# LionIRVT-ADC.net
KiCad netlist of a schematic drawn in Altium Designer
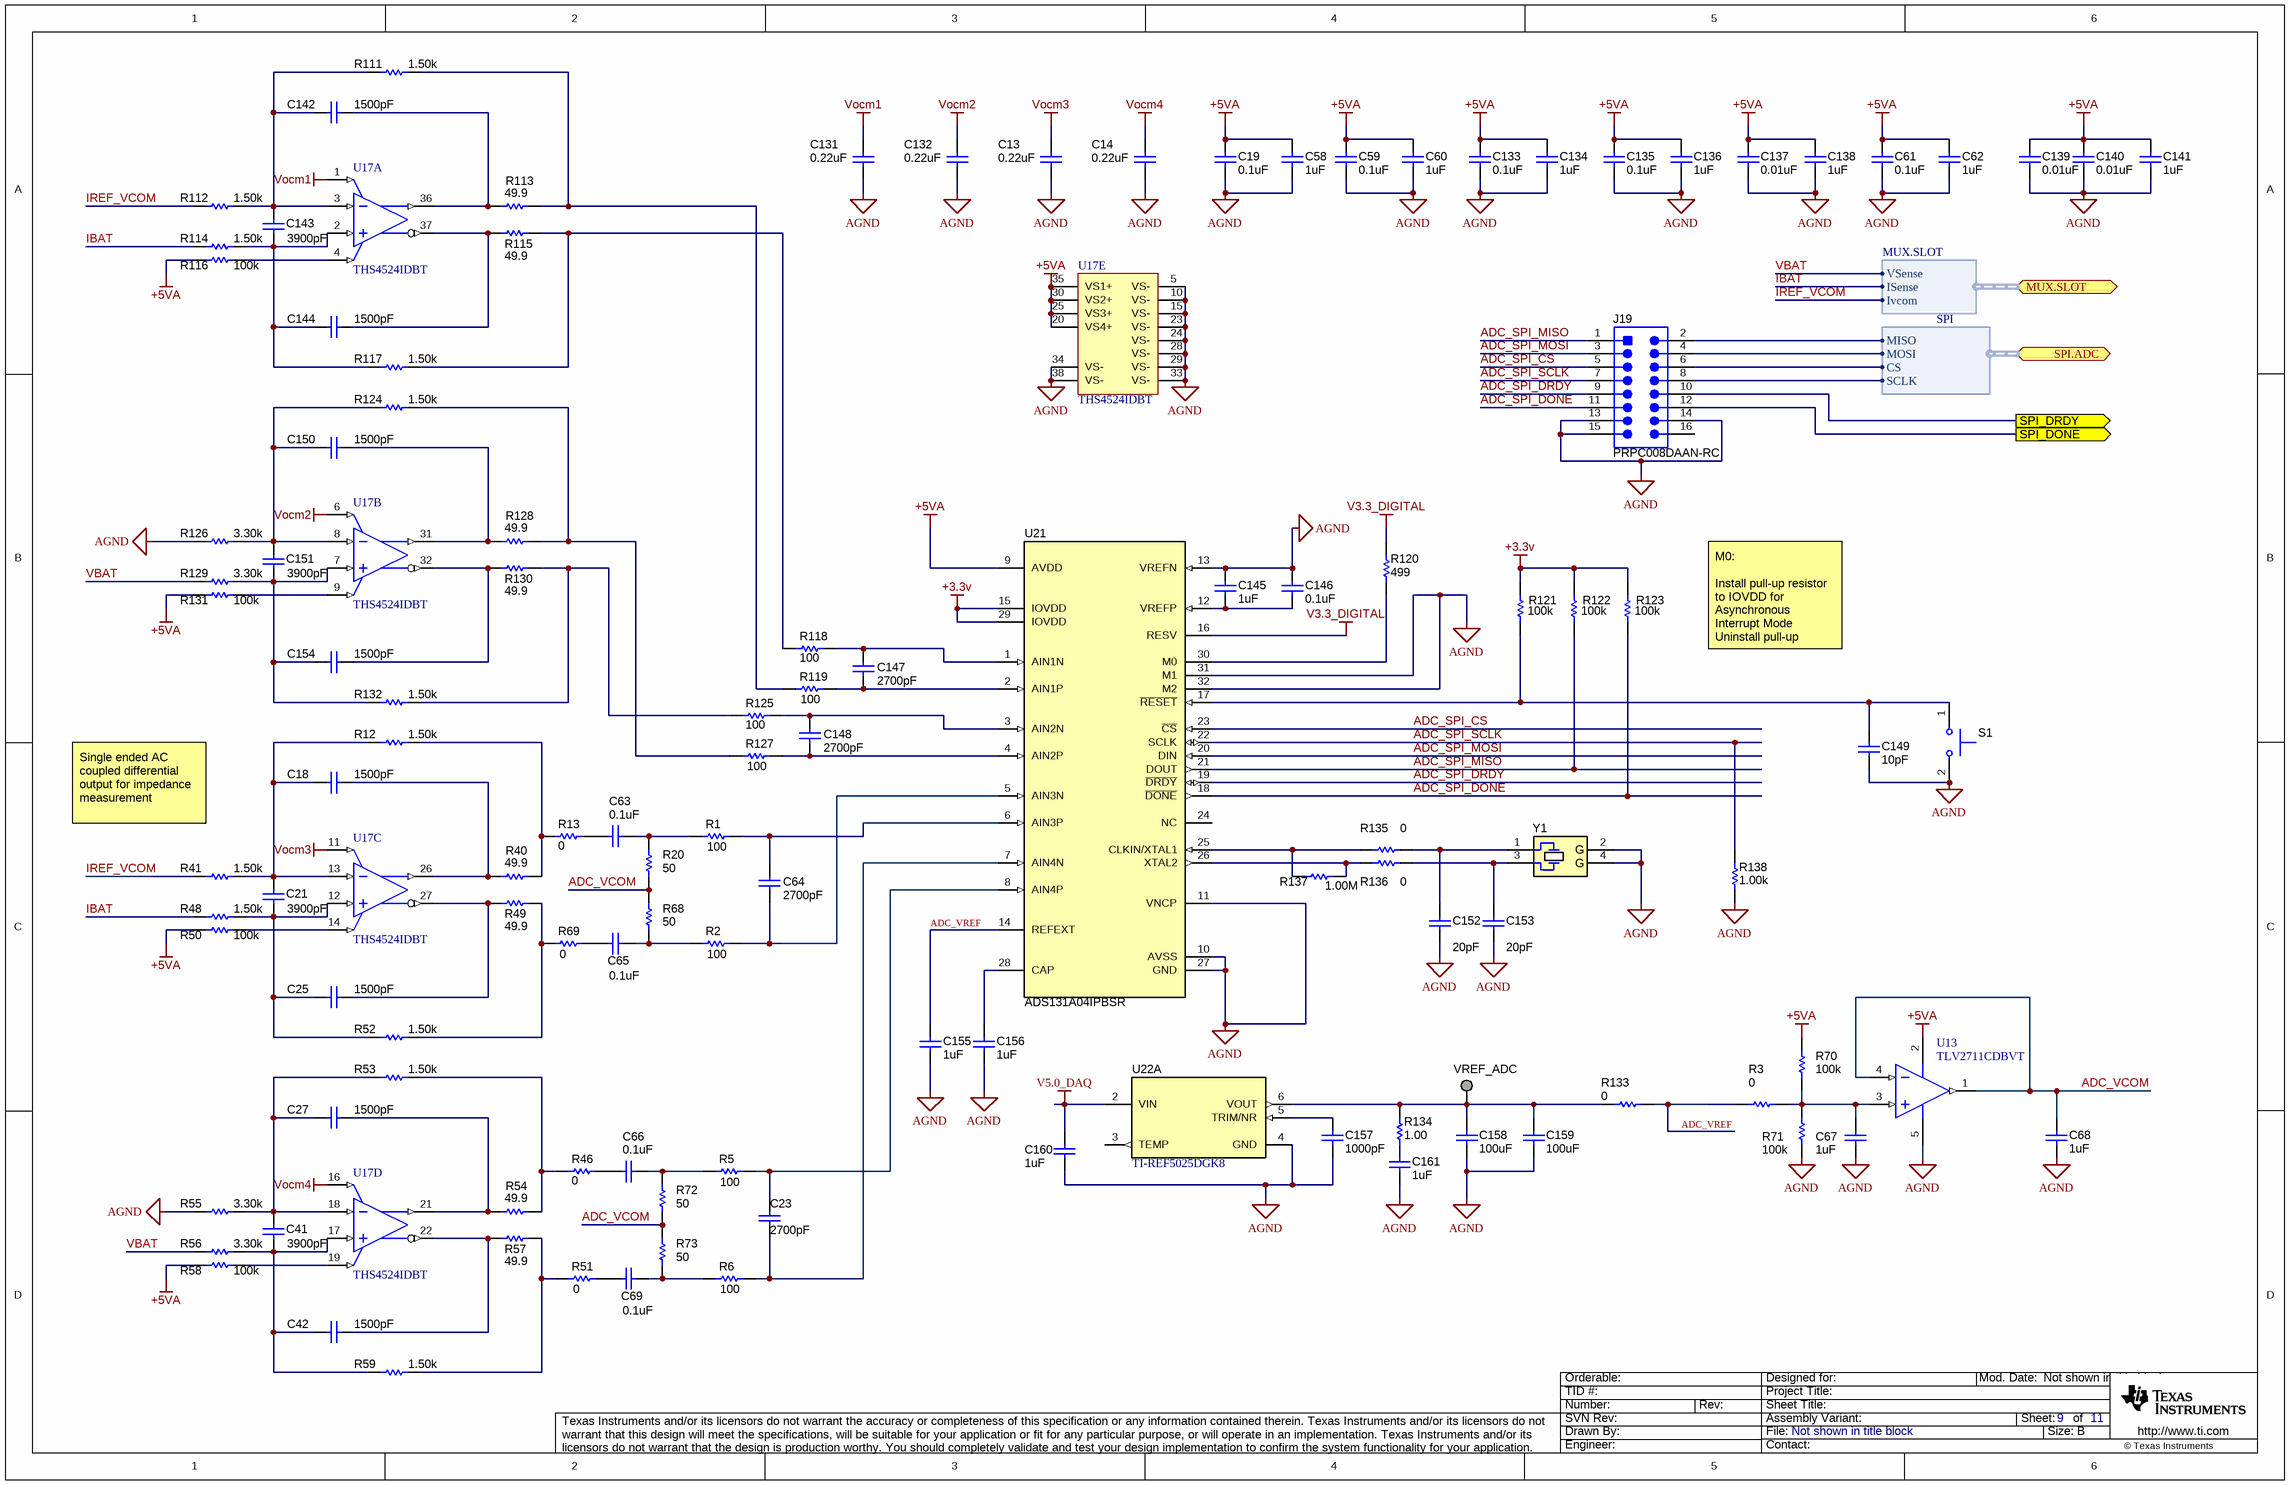
[diagram p0: LionIRVT-ADC.SchDoc]

(export (version "E")
  (design (tool "Eeschema 10.0.6"))
  (components
    (comp (ref "C13")
      (value "Capacitor")
      (footprint "0603C")
      (description "CAP, CERM, 0.22 uF, 16 V, +/- 10%, X7R, 0603")
      (fields
        (field (name "PARTNUMBER") "C0603C224K4RACTU")
        (field (name "VALUEDISPLAYED") "0.22uF")
        (field (name "MANUFACTURER") "Kemet")
        (field (name "PUBLISHER") "Texas Instruments")
      )
      (libsource (lib "SV601272A") (part "CMP-0006903-4"))
    )
    (comp (ref "C14")
      (value "Capacitor")
      (footprint "0603C")
      (description "CAP, CERM, 0.22 uF, 16 V, +/- 10%, X7R, 0603")
      (fields
        (field (name "PARTNUMBER") "C0603C224K4RACTU")
        (field (name "VALUEDISPLAYED") "0.22uF")
        (field (name "MANUFACTURER") "Kemet")
        (field (name "PUBLISHER") "Texas Instruments")
      )
      (libsource (lib "SV601272A") (part "CMP-0006903-4"))
    )
    (comp (ref "C18")
      (value "Capacitor")
      (footprint "0603C")
      (description "CAP, CERM, 1500 pF, 100 V, +/- 5%, X7R, 0603")
      (fields
        (field (name "PARTNUMBER") "06031C152JAT2A")
        (field (name "VALUEDISPLAYED") "1500pF")
        (field (name "MANUFACTURER") "AVX")
        (field (name "PUBLISHER") "Texas Instruments")
      )
      (libsource (lib "SV601272A") (part "Capacitor"))
    )
    (comp (ref "C19")
      (value "Capacitor")
      (footprint "0603C")
      (description "CAP, CERM, 0.1 uF, 25 V, +/- 5%, X7R, 0603")
      (fields
        (field (name "PARTNUMBER") "06033C104JAT2A")
        (field (name "VALUEDISPLAYED") "0.1uF")
        (field (name "MANUFACTURER") "AVX")
        (field (name "PUBLISHER") "Texas Instruments")
      )
      (libsource (lib "SV601272A") (part "CMP-0006752-5"))
    )
    (comp (ref "C21")
      (value "GRM188R72A392KA01D")
      (footprint "0603C")
      (description "CAP, CERM, 3900 pF, 100 V, +/- 10%, X7R, 0603")
      (fields
        (field (name "MANUFACTURER") "MuRata")
        (field (name "VALUEDISPLAYED") "3900pF")
        (field (name "PUBLISHER") "Texas Instruments")
      )
      (libsource (lib "SV601272A") (part "CMP-0007481-5"))
    )
    (comp (ref "C23")
      (value "Capacitor")
      (footprint "0603C")
      (description "CAP, CERM, 2700 pF, 50 V, +/- 5%, C0G/NP0, 0603")
      (fields
        (field (name "PARTNUMBER") "GRM1885C1H272JA01D")
        (field (name "VALUEDISPLAYED") "2700pF")
        (field (name "MANUFACTURER") "MuRata")
        (field (name "PUBLISHER") "Texas Instruments")
      )
      (libsource (lib "SV601272A") (part "Capacitor"))
    )
    (comp (ref "C25")
      (value "Capacitor")
      (footprint "0603C")
      (description "CAP, CERM, 1500 pF, 100 V, +/- 5%, X7R, 0603")
      (fields
        (field (name "PARTNUMBER") "06031C152JAT2A")
        (field (name "VALUEDISPLAYED") "1500pF")
        (field (name "MANUFACTURER") "AVX")
        (field (name "PUBLISHER") "Texas Instruments")
      )
      (libsource (lib "SV601272A") (part "Capacitor"))
    )
    (comp (ref "C27")
      (value "Capacitor")
      (footprint "0603C")
      (description "CAP, CERM, 1500 pF, 100 V, +/- 5%, X7R, 0603")
      (fields
        (field (name "PARTNUMBER") "06031C152JAT2A")
        (field (name "VALUEDISPLAYED") "1500pF")
        (field (name "MANUFACTURER") "AVX")
        (field (name "PUBLISHER") "Texas Instruments")
      )
      (libsource (lib "SV601272A") (part "Capacitor"))
    )
    (comp (ref "C41")
      (value "GRM188R72A392KA01D")
      (footprint "0603C")
      (description "CAP, CERM, 3900 pF, 100 V, +/- 10%, X7R, 0603")
      (fields
        (field (name "MANUFACTURER") "MuRata")
        (field (name "VALUEDISPLAYED") "3900pF")
        (field (name "PUBLISHER") "Texas Instruments")
      )
      (libsource (lib "SV601272A") (part "CMP-0007481-5"))
    )
    (comp (ref "C42")
      (value "Capacitor")
      (footprint "0603C")
      (description "CAP, CERM, 1500 pF, 100 V, +/- 5%, X7R, 0603")
      (fields
        (field (name "PARTNUMBER") "06031C152JAT2A")
        (field (name "VALUEDISPLAYED") "1500pF")
        (field (name "MANUFACTURER") "AVX")
        (field (name "PUBLISHER") "Texas Instruments")
      )
      (libsource (lib "SV601272A") (part "Capacitor"))
    )
    (comp (ref "C58")
      (value "Capacitor")
      (footprint "0603C")
      (description "CAP, CERM, 1 uF, 25 V, +/- 10%, X7R, 0603")
      (fields
        (field (name "PARTNUMBER") "GRM188R71E105KA12D")
        (field (name "VALUEDISPLAYED") "1uF")
        (field (name "MANUFACTURER") "MuRata")
        (field (name "PUBLISHER") "Texas Instruments")
      )
      (libsource (lib "SV601272A") (part "CMP-0007405-4"))
    )
    (comp (ref "C59")
      (value "Capacitor")
      (footprint "0603C")
      (description "CAP, CERM, 0.1 uF, 25 V, +/- 5%, X7R, 0603")
      (fields
        (field (name "PARTNUMBER") "06033C104JAT2A")
        (field (name "VALUEDISPLAYED") "0.1uF")
        (field (name "MANUFACTURER") "AVX")
        (field (name "PUBLISHER") "Texas Instruments")
      )
      (libsource (lib "SV601272A") (part "CMP-0006752-5"))
    )
    (comp (ref "C60")
      (value "Capacitor")
      (footprint "0603C")
      (description "CAP, CERM, 1 uF, 25 V, +/- 10%, X7R, 0603")
      (fields
        (field (name "PARTNUMBER") "GRM188R71E105KA12D")
        (field (name "VALUEDISPLAYED") "1uF")
        (field (name "MANUFACTURER") "MuRata")
        (field (name "PUBLISHER") "Texas Instruments")
      )
      (libsource (lib "SV601272A") (part "CMP-0007405-4"))
    )
    (comp (ref "C61")
      (value "Capacitor")
      (footprint "0603C")
      (description "CAP, CERM, 0.1 uF, 25 V, +/- 5%, X7R, 0603")
      (fields
        (field (name "PARTNUMBER") "06033C104JAT2A")
        (field (name "VALUEDISPLAYED") "0.1uF")
        (field (name "MANUFACTURER") "AVX")
        (field (name "PUBLISHER") "Texas Instruments")
      )
      (libsource (lib "SV601272A") (part "CMP-0006752-5"))
    )
    (comp (ref "C62")
      (value "Capacitor")
      (footprint "0603C")
      (description "CAP, CERM, 1 uF, 25 V, +/- 10%, X7R, 0603")
      (fields
        (field (name "PARTNUMBER") "GRM188R71E105KA12D")
        (field (name "VALUEDISPLAYED") "1uF")
        (field (name "MANUFACTURER") "MuRata")
        (field (name "PUBLISHER") "Texas Instruments")
      )
      (libsource (lib "SV601272A") (part "CMP-0007405-4"))
    )
    (comp (ref "C63")
      (value "Capacitor")
      (footprint "0603C")
      (description "CAP, CERM, 2700 pF, 50 V, +/- 5%, C0G/NP0, 0603")
      (fields
        (field (name "PARTNUMBER") "GRM1885C1H272JA01D")
        (field (name "VALUEDISPLAYED") "0.1uF")
        (field (name "MANUFACTURER") "MuRata")
        (field (name "PUBLISHER") "Texas Instruments")
      )
      (libsource (lib "SV601272A") (part "Capacitor"))
    )
    (comp (ref "C64")
      (value "Capacitor")
      (footprint "0603C")
      (description "CAP, CERM, 2700 pF, 50 V, +/- 5%, C0G/NP0, 0603")
      (fields
        (field (name "PARTNUMBER") "GRM1885C1H272JA01D")
        (field (name "VALUEDISPLAYED") "2700pF")
        (field (name "MANUFACTURER") "MuRata")
        (field (name "PUBLISHER") "Texas Instruments")
      )
      (libsource (lib "SV601272A") (part "Capacitor"))
    )
    (comp (ref "C65")
      (value "Capacitor")
      (footprint "0603C")
      (description "CAP, CERM, 2700 pF, 50 V, +/- 5%, C0G/NP0, 0603")
      (fields
        (field (name "PARTNUMBER") "GRM1885C1H272JA01D")
        (field (name "VALUEDISPLAYED") "0.1uF")
        (field (name "MANUFACTURER") "MuRata")
        (field (name "PUBLISHER") "Texas Instruments")
      )
      (libsource (lib "SV601272A") (part "Capacitor"))
    )
    (comp (ref "C66")
      (value "Capacitor")
      (footprint "0603C")
      (description "CAP, CERM, 2700 pF, 50 V, +/- 5%, C0G/NP0, 0603")
      (fields
        (field (name "PARTNUMBER") "GRM1885C1H272JA01D")
        (field (name "VALUEDISPLAYED") "0.1uF")
        (field (name "MANUFACTURER") "MuRata")
        (field (name "PUBLISHER") "Texas Instruments")
      )
      (libsource (lib "SV601272A") (part "Capacitor"))
    )
    (comp (ref "C67")
      (value "Capacitor")
      (footprint "0603C")
      (description "CAP, CERM, 1 uF, 25 V, +/- 10%, X7R, 0603")
      (fields
        (field (name "PARTNUMBER") "GRM188R71E105KA12D")
        (field (name "VALUEDISPLAYED") "1uF")
        (field (name "MANUFACTURER") "MuRata")
        (field (name "PUBLISHER") "Texas Instruments")
      )
      (libsource (lib "SV601272A") (part "Capacitor"))
    )
    (comp (ref "C68")
      (value "Capacitor")
      (footprint "0603C")
      (description "CAP, CERM, 1 uF, 25 V, +/- 10%, X7R, 0603")
      (fields
        (field (name "PARTNUMBER") "GRM188R71E105KA12D")
        (field (name "VALUEDISPLAYED") "1uF")
        (field (name "MANUFACTURER") "MuRata")
        (field (name "PUBLISHER") "Texas Instruments")
      )
      (libsource (lib "PMP40182") (part "Capacitor"))
    )
    (comp (ref "C69")
      (value "Capacitor")
      (footprint "0603C")
      (description "CAP, CERM, 2700 pF, 50 V, +/- 5%, C0G/NP0, 0603")
      (fields
        (field (name "PARTNUMBER") "GRM1885C1H272JA01D")
        (field (name "VALUEDISPLAYED") "0.1uF")
        (field (name "MANUFACTURER") "MuRata")
        (field (name "PUBLISHER") "Texas Instruments")
      )
      (libsource (lib "SV601272A") (part "Capacitor"))
    )
    (comp (ref "C131")
      (value "Capacitor")
      (footprint "0603C")
      (description "CAP, CERM, 0.22 uF, 16 V, +/- 10%, X7R, 0603")
      (fields
        (field (name "PARTNUMBER") "C0603C224K4RACTU")
        (field (name "VALUEDISPLAYED") "0.22uF")
        (field (name "MANUFACTURER") "Kemet")
        (field (name "PUBLISHER") "Texas Instruments")
      )
      (libsource (lib "SV601272A") (part "CMP-0006903-4"))
    )
    (comp (ref "C132")
      (value "Capacitor")
      (footprint "0603C")
      (description "CAP, CERM, 0.22 uF, 16 V, +/- 10%, X7R, 0603")
      (fields
        (field (name "PARTNUMBER") "C0603C224K4RACTU")
        (field (name "VALUEDISPLAYED") "0.22uF")
        (field (name "MANUFACTURER") "Kemet")
        (field (name "PUBLISHER") "Texas Instruments")
      )
      (libsource (lib "SV601272A") (part "CMP-0006903-4"))
    )
    (comp (ref "C133")
      (value "Capacitor")
      (footprint "0603C")
      (description "CAP, CERM, 0.1 uF, 25 V, +/- 5%, X7R, 0603")
      (fields
        (field (name "PARTNUMBER") "06033C104JAT2A")
        (field (name "VALUEDISPLAYED") "0.1uF")
        (field (name "MANUFACTURER") "AVX")
        (field (name "PUBLISHER") "Texas Instruments")
      )
      (libsource (lib "SV601272A") (part "CMP-0006752-5"))
    )
    (comp (ref "C134")
      (value "Capacitor")
      (footprint "0603C")
      (description "CAP, CERM, 1 uF, 25 V, +/- 10%, X7R, 0603")
      (fields
        (field (name "PARTNUMBER") "GRM188R71E105KA12D")
        (field (name "VALUEDISPLAYED") "1uF")
        (field (name "MANUFACTURER") "MuRata")
        (field (name "PUBLISHER") "Texas Instruments")
      )
      (libsource (lib "SV601272A") (part "CMP-0007405-4"))
    )
    (comp (ref "C135")
      (value "Capacitor")
      (footprint "0603C")
      (description "CAP, CERM, 0.1 uF, 25 V, +/- 5%, X7R, 0603")
      (fields
        (field (name "PARTNUMBER") "06033C104JAT2A")
        (field (name "VALUEDISPLAYED") "0.1uF")
        (field (name "MANUFACTURER") "AVX")
        (field (name "PUBLISHER") "Texas Instruments")
      )
      (libsource (lib "SV601272A") (part "CMP-0006752-5"))
    )
    (comp (ref "C136")
      (value "Capacitor")
      (footprint "0603C")
      (description "CAP, CERM, 1 uF, 25 V, +/- 10%, X7R, 0603")
      (fields
        (field (name "PARTNUMBER") "GRM188R71E105KA12D")
        (field (name "VALUEDISPLAYED") "1uF")
        (field (name "MANUFACTURER") "MuRata")
        (field (name "PUBLISHER") "Texas Instruments")
      )
      (libsource (lib "SV601272A") (part "CMP-0007405-4"))
    )
    (comp (ref "C137")
      (value "Capacitor")
      (footprint "0603C")
      (description "CAP, CERM, 0.01 uF, 100 V, +/- 10%, X7R, 0603")
      (fields
        (field (name "PARTNUMBER") "06031C103KAT2A")
        (field (name "VALUEDISPLAYED") "0.01uF")
        (field (name "MANUFACTURER") "AVX")
        (field (name "PUBLISHER") "Texas Instruments")
      )
      (libsource (lib "SV601272A") (part "CMP-0006727-4"))
    )
    (comp (ref "C138")
      (value "Capacitor")
      (footprint "0603C")
      (description "CAP, CERM, 1 uF, 25 V, +/- 10%, X7R, 0603")
      (fields
        (field (name "PARTNUMBER") "GRM188R71E105KA12D")
        (field (name "VALUEDISPLAYED") "1uF")
        (field (name "MANUFACTURER") "MuRata")
        (field (name "PUBLISHER") "Texas Instruments")
      )
      (libsource (lib "SV601272A") (part "CMP-0007405-4"))
    )
    (comp (ref "C139")
      (value "Capacitor")
      (footprint "0603C")
      (description "CAP, CERM, 0.01 uF, 100 V, +/- 10%, X7R, 0603")
      (fields
        (field (name "PARTNUMBER") "06031C103KAT2A")
        (field (name "VALUEDISPLAYED") "0.01uF")
        (field (name "MANUFACTURER") "AVX")
        (field (name "PUBLISHER") "Texas Instruments")
      )
      (libsource (lib "SV601272A") (part "CMP-0006727-4"))
    )
    (comp (ref "C140")
      (value "Capacitor")
      (footprint "0603C")
      (description "CAP, CERM, 0.01 uF, 100 V, +/- 10%, X7R, 0603")
      (fields
        (field (name "PARTNUMBER") "06031C103KAT2A")
        (field (name "VALUEDISPLAYED") "0.01uF")
        (field (name "MANUFACTURER") "AVX")
        (field (name "PUBLISHER") "Texas Instruments")
      )
      (libsource (lib "SV601272A") (part "CMP-0006727-4"))
    )
    (comp (ref "C141")
      (value "Capacitor")
      (footprint "0603C")
      (description "CAP, CERM, 1 uF, 25 V, +/- 10%, X7R, 0603")
      (fields
        (field (name "PARTNUMBER") "GRM188R71E105KA12D")
        (field (name "VALUEDISPLAYED") "1uF")
        (field (name "MANUFACTURER") "MuRata")
        (field (name "PUBLISHER") "Texas Instruments")
      )
      (libsource (lib "SV601272A") (part "CMP-0007405-4"))
    )
    (comp (ref "C142")
      (value "Capacitor")
      (footprint "0603C")
      (description "CAP, CERM, 1500 pF, 100 V, +/- 5%, X7R, 0603")
      (fields
        (field (name "PARTNUMBER") "06031C152JAT2A")
        (field (name "VALUEDISPLAYED") "1500pF")
        (field (name "MANUFACTURER") "AVX")
        (field (name "PUBLISHER") "Texas Instruments")
      )
      (libsource (lib "SV601272A") (part "Capacitor"))
    )
    (comp (ref "C143")
      (value "GRM188R72A392KA01D")
      (footprint "0603C")
      (description "CAP, CERM, 3900 pF, 100 V, +/- 10%, X7R, 0603")
      (fields
        (field (name "MANUFACTURER") "MuRata")
        (field (name "VALUEDISPLAYED") "3900pF")
        (field (name "PUBLISHER") "Texas Instruments")
      )
      (libsource (lib "SV601272A") (part "CMP-0007481-5"))
    )
    (comp (ref "C144")
      (value "Capacitor")
      (footprint "0603C")
      (description "CAP, CERM, 1500 pF, 100 V, +/- 5%, X7R, 0603")
      (fields
        (field (name "PARTNUMBER") "06031C152JAT2A")
        (field (name "VALUEDISPLAYED") "1500pF")
        (field (name "MANUFACTURER") "AVX")
        (field (name "PUBLISHER") "Texas Instruments")
      )
      (libsource (lib "SV601272A") (part "Capacitor"))
    )
    (comp (ref "C145")
      (value "Capacitor")
      (footprint "0603C")
      (description "CAP, CERM, 1 uF, 25 V, +/- 10%, X7R, 0603")
      (fields
        (field (name "PARTNUMBER") "GRM188R71E105KA12D")
        (field (name "VALUEDISPLAYED") "1uF")
        (field (name "MANUFACTURER") "MuRata")
        (field (name "PUBLISHER") "Texas Instruments")
      )
      (libsource (lib "SV601272A") (part "Capacitor"))
    )
    (comp (ref "C146")
      (value "Capacitor")
      (footprint "0603C")
      (description "CAP, CERM, 0.1 uF, 25 V, +/- 5%, X7R, 0603")
      (fields
        (field (name "PARTNUMBER") "06033C104JAT2A")
        (field (name "VALUEDISPLAYED") "0.1uF")
        (field (name "MANUFACTURER") "AVX")
        (field (name "PUBLISHER") "Texas Instruments")
      )
      (libsource (lib "SV601272A") (part "Capacitor"))
    )
    (comp (ref "C147")
      (value "Capacitor")
      (footprint "0603C")
      (description "CAP, CERM, 2700 pF, 50 V, +/- 5%, C0G/NP0, 0603")
      (fields
        (field (name "PARTNUMBER") "GRM1885C1H272JA01D")
        (field (name "VALUEDISPLAYED") "2700pF")
        (field (name "MANUFACTURER") "MuRata")
        (field (name "PUBLISHER") "Texas Instruments")
      )
      (libsource (lib "SV601272A") (part "Capacitor"))
    )
    (comp (ref "C148")
      (value "Capacitor")
      (footprint "0603C")
      (description "CAP, CERM, 2700 pF, 50 V, +/- 5%, C0G/NP0, 0603")
      (fields
        (field (name "PARTNUMBER") "GRM1885C1H272JA01D")
        (field (name "VALUEDISPLAYED") "2700pF")
        (field (name "MANUFACTURER") "MuRata")
        (field (name "PUBLISHER") "Texas Instruments")
      )
      (libsource (lib "SV601272A") (part "Capacitor"))
    )
    (comp (ref "C149")
      (value "Capacitor")
      (footprint "0603C")
      (description "CAP, CERM, 10 pF, 50 V, +/- 5%, C0G/NP0, 0603")
      (fields
        (field (name "PARTNUMBER") "06035A100JAT2A")
        (field (name "VALUEDISPLAYED") "10pF")
        (field (name "MANUFACTURER") "AVX")
        (field (name "PUBLISHER") "Texas Instruments")
      )
      (libsource (lib "SV601272A") (part "Capacitor"))
    )
    (comp (ref "C150")
      (value "Capacitor")
      (footprint "0603C")
      (description "CAP, CERM, 1500 pF, 100 V, +/- 5%, X7R, 0603")
      (fields
        (field (name "PARTNUMBER") "06031C152JAT2A")
        (field (name "VALUEDISPLAYED") "1500pF")
        (field (name "MANUFACTURER") "AVX")
        (field (name "PUBLISHER") "Texas Instruments")
      )
      (libsource (lib "SV601272A") (part "Capacitor"))
    )
    (comp (ref "C151")
      (value "GRM188R72A392KA01D")
      (footprint "0603C")
      (description "CAP, CERM, 3900 pF, 100 V, +/- 10%, X7R, 0603")
      (fields
        (field (name "MANUFACTURER") "MuRata")
        (field (name "VALUEDISPLAYED") "3900pF")
        (field (name "PUBLISHER") "Texas Instruments")
      )
      (libsource (lib "SV601272A") (part "CMP-0007481-5"))
    )
    (comp (ref "C152")
      (value "GRM1885C1H200JA01D")
      (footprint "0603C")
      (description "CAP, CERM, 20 pF, 50 V, +/- 5%, C0G/NP0, 0603")
      (fields
        (field (name "MANUFACTURER") "MuRata")
        (field (name "VALUEDISPLAYED") "20pF")
        (field (name "PUBLISHER") "Texas Instruments")
      )
      (libsource (lib "SV601272A") (part "CMP-0007193-4"))
    )
    (comp (ref "C153")
      (value "GRM1885C1H200JA01D")
      (footprint "0603C")
      (description "CAP, CERM, 20 pF, 50 V, +/- 5%, C0G/NP0, 0603")
      (fields
        (field (name "MANUFACTURER") "MuRata")
        (field (name "VALUEDISPLAYED") "20pF")
        (field (name "PUBLISHER") "Texas Instruments")
      )
      (libsource (lib "SV601272A") (part "CMP-0007193-4"))
    )
    (comp (ref "C154")
      (value "Capacitor")
      (footprint "0603C")
      (description "CAP, CERM, 1500 pF, 100 V, +/- 5%, X7R, 0603")
      (fields
        (field (name "PARTNUMBER") "06031C152JAT2A")
        (field (name "VALUEDISPLAYED") "1500pF")
        (field (name "MANUFACTURER") "AVX")
        (field (name "PUBLISHER") "Texas Instruments")
      )
      (libsource (lib "SV601272A") (part "Capacitor"))
    )
    (comp (ref "C155")
      (value "Capacitor")
      (footprint "0603C")
      (description "CAP, CERM, 1 uF, 25 V, +/- 10%, X7R, 0603")
      (fields
        (field (name "PARTNUMBER") "GRM188R71E105KA12D")
        (field (name "VALUEDISPLAYED") "1uF")
        (field (name "MANUFACTURER") "MuRata")
        (field (name "PUBLISHER") "Texas Instruments")
      )
      (libsource (lib "SV601272A") (part "Capacitor"))
    )
    (comp (ref "C156")
      (value "Capacitor")
      (footprint "0603C")
      (description "CAP, CERM, 1 uF, 25 V, +/- 10%, X7R, 0603")
      (fields
        (field (name "PARTNUMBER") "GRM188R71E105KA12D")
        (field (name "VALUEDISPLAYED") "1uF")
        (field (name "MANUFACTURER") "MuRata")
        (field (name "PUBLISHER") "Texas Instruments")
      )
      (libsource (lib "SV601272A") (part "Capacitor"))
    )
    (comp (ref "C157")
      (value "Capacitor")
      (footprint "0603C")
      (description "CAP, CERM, 1000 pF, 100 V, +/- 5%, X7R, 0603")
      (fields
        (field (name "PARTNUMBER") "06031C102JAT2A")
        (field (name "VALUEDISPLAYED") "1000pF")
        (field (name "MANUFACTURER") "AVX")
        (field (name "PUBLISHER") "Texas Instruments")
      )
      (libsource (lib "SV601272A") (part "Capacitor"))
    )
    (comp (ref "C158")
      (value "Capacitor")
      (footprint "1206_190")
      (description "CAP, CERM, 100 uF, 10 V, +/- 20%, X5R, 1206_190")
      (fields
        (field (name "PARTNUMBER") "C3216X5R1A107M160AC")
        (field (name "VALUEDISPLAYED") "100uF")
        (field (name "MANUFACTURER") "TDK")
        (field (name "PUBLISHER") "Texas Instruments")
      )
      (libsource (lib "SV601272A") (part "Capacitor"))
    )
    (comp (ref "C159")
      (value "Capacitor")
      (footprint "1206_190")
      (description "CAP, CERM, 100 uF, 10 V, +/- 20%, X5R, 1206_190")
      (fields
        (field (name "PARTNUMBER") "C3216X5R1A107M160AC")
        (field (name "VALUEDISPLAYED") "100uF")
        (field (name "MANUFACTURER") "TDK")
        (field (name "PUBLISHER") "Texas Instruments")
      )
      (libsource (lib "SV601272A") (part "Capacitor"))
    )
    (comp (ref "C160")
      (value "Capacitor")
      (footprint "0603C")
      (description "CAP, CERM, 1 uF, 25 V, +/- 10%, X7R, 0603")
      (fields
        (field (name "PARTNUMBER") "GRM188R71E105KA12D")
        (field (name "VALUEDISPLAYED") "1uF")
        (field (name "MANUFACTURER") "MuRata")
        (field (name "PUBLISHER") "Texas Instruments")
      )
      (libsource (lib "SV601272A") (part "Capacitor"))
    )
    (comp (ref "C161")
      (value "Capacitor")
      (footprint "0603C")
      (description "CAP, CERM, 1 uF, 25 V, +/- 10%, X7R, 0603")
      (fields
        (field (name "PARTNUMBER") "GRM188R71E105KA12D")
        (field (name "VALUEDISPLAYED") "1uF")
        (field (name "MANUFACTURER") "MuRata")
        (field (name "PUBLISHER") "Texas Instruments")
      )
      (libsource (lib "SV601272A") (part "Capacitor"))
    )
    (comp (ref "J19")
      (value "PRPC008DAAN-RC")
      (footprint "Sullins_xxxC008DAAN")
      (description "Header, 2.54mm, 8x2, Gold, TH")
      (fields
        (field (name "MANUFACTURER") "Sullins Connector Solutions")
        (field (name "PUBLISHER") "Texas Instruments")
      )
      (libsource (lib "SV601272A") (part "CMP-0054590-1"))
    )
    (comp (ref "R1")
      (value "Resistor")
      (footprint "0603R")
      (description "RES, 100, 1%, 0.1 W, AEC-Q200 Grade 0, 0603")
      (fields
        (field (name "PARTNUMBER") "CRCW0603100RFKEA")
        (field (name "MANUFACTURER") "Vishay-Dale")
        (field (name "VALUEDISPLAYED") "100")
      )
      (libsource (lib "SV601272A") (part "CMP-0021991-4"))
    )
    (comp (ref "R2")
      (value "Resistor")
      (footprint "0603R")
      (description "RES, 100, 1%, 0.1 W, AEC-Q200 Grade 0, 0603")
      (fields
        (field (name "PARTNUMBER") "CRCW0603100RFKEA")
        (field (name "MANUFACTURER") "Vishay-Dale")
        (field (name "VALUEDISPLAYED") "100")
      )
      (libsource (lib "SV601272A") (part "CMP-0021991-4"))
    )
    (comp (ref "R3")
      (value "Resistor")
      (footprint "0603R")
      (description "RES, 0, 5%, 0.1 W, 0603")
      (fields
        (field (name "PARTNUMBER") "ERJ-3GEY0R00V")
        (field (name "MANUFACTURER") "Panasonic")
        (field (name "VALUEDISPLAYED") "0")
        (field (name "PUBLISHER") "Texas Instruments")
      )
      (libsource (lib "SV601272A") (part "Resistor"))
    )
    (comp (ref "R5")
      (value "Resistor")
      (footprint "0603R")
      (description "RES, 100, 1%, 0.1 W, AEC-Q200 Grade 0, 0603")
      (fields
        (field (name "PARTNUMBER") "CRCW0603100RFKEA")
        (field (name "MANUFACTURER") "Vishay-Dale")
        (field (name "VALUEDISPLAYED") "100")
      )
      (libsource (lib "SV601272A") (part "CMP-0021991-4"))
    )
    (comp (ref "R6")
      (value "Resistor")
      (footprint "0603R")
      (description "RES, 100, 1%, 0.1 W, AEC-Q200 Grade 0, 0603")
      (fields
        (field (name "PARTNUMBER") "CRCW0603100RFKEA")
        (field (name "MANUFACTURER") "Vishay-Dale")
        (field (name "VALUEDISPLAYED") "100")
      )
      (libsource (lib "SV601272A") (part "CMP-0021991-4"))
    )
    (comp (ref "R12")
      (value "RC0603FR-071K5L")
      (footprint "0603R")
      (description "RES, 1.50 k, 1%, 0.1 W, 0603")
      (fields
        (field (name "MANUFACTURER") "Yageo America")
        (field (name "VALUEDISPLAYED") "1.50k")
        (field (name "PUBLISHER") "Texas Instruments")
      )
      (libsource (lib "SV601272A") (part "CMP-0022883-3"))
    )
    (comp (ref "R13")
      (value "Resistor")
      (footprint "0603R")
      (description "RES, 100, 1%, 0.1 W, AEC-Q200 Grade 0, 0603")
      (fields
        (field (name "PARTNUMBER") "CRCW0603100RFKEA")
        (field (name "MANUFACTURER") "Vishay-Dale")
        (field (name "VALUEDISPLAYED") "0")
      )
      (libsource (lib "SV601272A") (part "CMP-0021991-4"))
    )
    (comp (ref "R20")
      (value "Resistor")
      (footprint "0603R")
      (description "RES, 100, 1%, 0.1 W, AEC-Q200 Grade 0, 0603")
      (fields
        (field (name "PARTNUMBER") "CRCW0603100RFKEA")
        (field (name "MANUFACTURER") "Vishay-Dale")
        (field (name "VALUEDISPLAYED") "50")
      )
      (libsource (lib "SV601272A") (part "CMP-0021991-4"))
    )
    (comp (ref "R40")
      (value "Resistor")
      (footprint "0603R")
      (description "RES, 49.9, 1%, 0.1 W, AEC-Q200 Grade 0, 0603")
      (fields
        (field (name "PARTNUMBER") "CRCW060349R9FKEA")
        (field (name "MANUFACTURER") "Vishay-Dale")
        (field (name "VALUEDISPLAYED") "49.9")
      )
      (libsource (lib "SV601272A") (part "CMP-0022448-4"))
    )
    (comp (ref "R41")
      (value "RC0603FR-071K5L")
      (footprint "0603R")
      (description "RES, 1.50 k, 1%, 0.1 W, 0603")
      (fields
        (field (name "MANUFACTURER") "Yageo America")
        (field (name "VALUEDISPLAYED") "1.50k")
        (field (name "PUBLISHER") "Texas Instruments")
      )
      (libsource (lib "SV601272A") (part "CMP-0022883-3"))
    )
    (comp (ref "R46")
      (value "Resistor")
      (footprint "0603R")
      (description "RES, 100, 1%, 0.1 W, AEC-Q200 Grade 0, 0603")
      (fields
        (field (name "PARTNUMBER") "CRCW0603100RFKEA")
        (field (name "MANUFACTURER") "Vishay-Dale")
        (field (name "VALUEDISPLAYED") "0")
      )
      (libsource (lib "SV601272A") (part "CMP-0021991-4"))
    )
    (comp (ref "R48")
      (value "RC0603FR-071K5L")
      (footprint "0603R")
      (description "RES, 1.50 k, 1%, 0.1 W, 0603")
      (fields
        (field (name "MANUFACTURER") "Yageo America")
        (field (name "VALUEDISPLAYED") "1.50k")
        (field (name "PUBLISHER") "Texas Instruments")
      )
      (libsource (lib "SV601272A") (part "CMP-0022883-3"))
    )
    (comp (ref "R49")
      (value "Resistor")
      (footprint "0603R")
      (description "RES, 49.9, 1%, 0.1 W, AEC-Q200 Grade 0, 0603")
      (fields
        (field (name "PARTNUMBER") "CRCW060349R9FKEA")
        (field (name "MANUFACTURER") "Vishay-Dale")
        (field (name "VALUEDISPLAYED") "49.9")
      )
      (libsource (lib "SV601272A") (part "CMP-0022448-4"))
    )
    (comp (ref "R50")
      (value "Resistor")
      (footprint "0603R")
      (description "RES, 100 k, 1%, 0.1 W, AEC-Q200 Grade 0, 0603")
      (fields
        (field (name "PARTNUMBER") "CRCW0603100KFKEA")
        (field (name "MANUFACTURER") "Vishay-Dale")
        (field (name "VALUEDISPLAYED") "100k")
      )
      (libsource (lib "SV601272A") (part "CMP-0021990-4"))
    )
    (comp (ref "R51")
      (value "Resistor")
      (footprint "0603R")
      (description "RES, 100, 1%, 0.1 W, AEC-Q200 Grade 0, 0603")
      (fields
        (field (name "PARTNUMBER") "CRCW0603100RFKEA")
        (field (name "MANUFACTURER") "Vishay-Dale")
        (field (name "VALUEDISPLAYED") "0")
      )
      (libsource (lib "SV601272A") (part "CMP-0021991-4"))
    )
    (comp (ref "R52")
      (value "RC0603FR-071K5L")
      (footprint "0603R")
      (description "RES, 1.50 k, 1%, 0.1 W, 0603")
      (fields
        (field (name "MANUFACTURER") "Yageo America")
        (field (name "VALUEDISPLAYED") "1.50k")
        (field (name "PUBLISHER") "Texas Instruments")
      )
      (libsource (lib "SV601272A") (part "CMP-0022883-3"))
    )
    (comp (ref "R53")
      (value "RC0603FR-071K5L")
      (footprint "0603R")
      (description "RES, 1.50 k, 1%, 0.1 W, 0603")
      (fields
        (field (name "MANUFACTURER") "Yageo America")
        (field (name "VALUEDISPLAYED") "1.50k")
        (field (name "PUBLISHER") "Texas Instruments")
      )
      (libsource (lib "SV601272A") (part "CMP-0022883-3"))
    )
    (comp (ref "R54")
      (value "Resistor")
      (footprint "0603R")
      (description "RES, 49.9, 1%, 0.1 W, AEC-Q200 Grade 0, 0603")
      (fields
        (field (name "PARTNUMBER") "CRCW060349R9FKEA")
        (field (name "MANUFACTURER") "Vishay-Dale")
        (field (name "VALUEDISPLAYED") "49.9")
      )
      (libsource (lib "SV601272A") (part "CMP-0022448-4"))
    )
    (comp (ref "R55")
      (value "RC0603FR-073K3L")
      (footprint "0603R")
      (description "RES, 3.30 k, 1%, 0.1 W, 0603")
      (fields
        (field (name "VALUEDISPLAYED") "3.30k")
        (field (name "MANUFACTURER") "Yageo America")
        (field (name "PUBLISHER") "Texas Instruments")
      )
      (libsource (lib "SV601272A") (part "Resistor"))
    )
    (comp (ref "R56")
      (value "RC0603FR-073K3L")
      (footprint "0603R")
      (description "RES, 3.30 k, 1%, 0.1 W, 0603")
      (fields
        (field (name "VALUEDISPLAYED") "3.30k")
        (field (name "MANUFACTURER") "Yageo America")
        (field (name "PUBLISHER") "Texas Instruments")
      )
      (libsource (lib "SV601272A") (part "Resistor"))
    )
    (comp (ref "R57")
      (value "Resistor")
      (footprint "0603R")
      (description "RES, 49.9, 1%, 0.1 W, AEC-Q200 Grade 0, 0603")
      (fields
        (field (name "PARTNUMBER") "CRCW060349R9FKEA")
        (field (name "MANUFACTURER") "Vishay-Dale")
        (field (name "VALUEDISPLAYED") "49.9")
      )
      (libsource (lib "SV601272A") (part "Resistor"))
    )
    (comp (ref "R58")
      (value "Resistor")
      (footprint "0603R")
      (description "RES, 100 k, 1%, 0.1 W, AEC-Q200 Grade 0, 0603")
      (fields
        (field (name "PARTNUMBER") "CRCW0603100KFKEA")
        (field (name "MANUFACTURER") "Vishay-Dale")
        (field (name "VALUEDISPLAYED") "100k")
      )
      (libsource (lib "SV601272A") (part "Resistor"))
    )
    (comp (ref "R59")
      (value "RC0603FR-071K5L")
      (footprint "0603R")
      (description "RES, 1.50 k, 1%, 0.1 W, 0603")
      (fields
        (field (name "MANUFACTURER") "Yageo America")
        (field (name "VALUEDISPLAYED") "1.50k")
        (field (name "PUBLISHER") "Texas Instruments")
      )
      (libsource (lib "SV601272A") (part "Resistor"))
    )
    (comp (ref "R68")
      (value "Resistor")
      (footprint "0603R")
      (description "RES, 100, 1%, 0.1 W, AEC-Q200 Grade 0, 0603")
      (fields
        (field (name "PARTNUMBER") "CRCW0603100RFKEA")
        (field (name "MANUFACTURER") "Vishay-Dale")
        (field (name "VALUEDISPLAYED") "50")
      )
      (libsource (lib "SV601272A") (part "CMP-0021991-4"))
    )
    (comp (ref "R69")
      (value "Resistor")
      (footprint "0603R")
      (description "RES, 100, 1%, 0.1 W, AEC-Q200 Grade 0, 0603")
      (fields
        (field (name "PARTNUMBER") "CRCW0603100RFKEA")
        (field (name "MANUFACTURER") "Vishay-Dale")
        (field (name "VALUEDISPLAYED") "0")
      )
      (libsource (lib "SV601272A") (part "CMP-0021991-4"))
    )
    (comp (ref "R70")
      (value "Resistor")
      (footprint "0603R")
      (description "RES, 100 k, 1%, 0.1 W, AEC-Q200 Grade 0, 0603")
      (fields
        (field (name "PARTNUMBER") "CRCW0603100KFKEA")
        (field (name "MANUFACTURER") "Vishay-Dale")
        (field (name "VALUEDISPLAYED") "100k")
      )
      (libsource (lib "SV601272A") (part "CMP-0021990-4"))
    )
    (comp (ref "R71")
      (value "Resistor")
      (footprint "0603R")
      (description "RES, 100 k, 1%, 0.1 W, AEC-Q200 Grade 0, 0603")
      (fields
        (field (name "PARTNUMBER") "CRCW0603100KFKEA")
        (field (name "MANUFACTURER") "Vishay-Dale")
        (field (name "VALUEDISPLAYED") "100k")
      )
      (libsource (lib "SV601272A") (part "CMP-0021990-4"))
    )
    (comp (ref "R72")
      (value "Resistor")
      (footprint "0603R")
      (description "RES, 100, 1%, 0.1 W, AEC-Q200 Grade 0, 0603")
      (fields
        (field (name "PARTNUMBER") "CRCW0603100RFKEA")
        (field (name "MANUFACTURER") "Vishay-Dale")
        (field (name "VALUEDISPLAYED") "50")
      )
      (libsource (lib "SV601272A") (part "CMP-0021991-4"))
    )
    (comp (ref "R73")
      (value "Resistor")
      (footprint "0603R")
      (description "RES, 100, 1%, 0.1 W, AEC-Q200 Grade 0, 0603")
      (fields
        (field (name "PARTNUMBER") "CRCW0603100RFKEA")
        (field (name "MANUFACTURER") "Vishay-Dale")
        (field (name "VALUEDISPLAYED") "50")
      )
      (libsource (lib "SV601272A") (part "CMP-0021991-4"))
    )
    (comp (ref "R111")
      (value "RC0603FR-071K5L")
      (footprint "0603R")
      (description "RES, 1.50 k, 1%, 0.1 W, 0603")
      (fields
        (field (name "MANUFACTURER") "Yageo America")
        (field (name "VALUEDISPLAYED") "1.50k")
        (field (name "PUBLISHER") "Texas Instruments")
      )
      (libsource (lib "SV601272A") (part "CMP-0022883-3"))
    )
    (comp (ref "R112")
      (value "RC0603FR-071K5L")
      (footprint "0603R")
      (description "RES, 1.50 k, 1%, 0.1 W, 0603")
      (fields
        (field (name "MANUFACTURER") "Yageo America")
        (field (name "VALUEDISPLAYED") "1.50k")
        (field (name "PUBLISHER") "Texas Instruments")
      )
      (libsource (lib "SV601272A") (part "CMP-0022883-3"))
    )
    (comp (ref "R113")
      (value "Resistor")
      (footprint "0603R")
      (description "RES, 49.9, 1%, 0.1 W, AEC-Q200 Grade 0, 0603")
      (fields
        (field (name "PARTNUMBER") "CRCW060349R9FKEA")
        (field (name "MANUFACTURER") "Vishay-Dale")
        (field (name "VALUEDISPLAYED") "49.9")
      )
      (libsource (lib "SV601272A") (part "CMP-0022448-4"))
    )
    (comp (ref "R114")
      (value "RC0603FR-071K5L")
      (footprint "0603R")
      (description "RES, 1.50 k, 1%, 0.1 W, 0603")
      (fields
        (field (name "MANUFACTURER") "Yageo America")
        (field (name "VALUEDISPLAYED") "1.50k")
        (field (name "PUBLISHER") "Texas Instruments")
      )
      (libsource (lib "SV601272A") (part "CMP-0022883-3"))
    )
    (comp (ref "R115")
      (value "Resistor")
      (footprint "0603R")
      (description "RES, 49.9, 1%, 0.1 W, AEC-Q200 Grade 0, 0603")
      (fields
        (field (name "PARTNUMBER") "CRCW060349R9FKEA")
        (field (name "MANUFACTURER") "Vishay-Dale")
        (field (name "VALUEDISPLAYED") "49.9")
      )
      (libsource (lib "SV601272A") (part "CMP-0022448-4"))
    )
    (comp (ref "R116")
      (value "Resistor")
      (footprint "0603R")
      (description "RES, 100 k, 1%, 0.1 W, AEC-Q200 Grade 0, 0603")
      (fields
        (field (name "PARTNUMBER") "CRCW0603100KFKEA")
        (field (name "MANUFACTURER") "Vishay-Dale")
        (field (name "VALUEDISPLAYED") "100k")
      )
      (libsource (lib "SV601272A") (part "CMP-0021990-4"))
    )
    (comp (ref "R117")
      (value "RC0603FR-071K5L")
      (footprint "0603R")
      (description "RES, 1.50 k, 1%, 0.1 W, 0603")
      (fields
        (field (name "MANUFACTURER") "Yageo America")
        (field (name "VALUEDISPLAYED") "1.50k")
        (field (name "PUBLISHER") "Texas Instruments")
      )
      (libsource (lib "SV601272A") (part "CMP-0022883-3"))
    )
    (comp (ref "R118")
      (value "Resistor")
      (footprint "0603R")
      (description "RES, 100, 1%, 0.1 W, AEC-Q200 Grade 0, 0603")
      (fields
        (field (name "PARTNUMBER") "CRCW0603100RFKEA")
        (field (name "MANUFACTURER") "Vishay-Dale")
        (field (name "VALUEDISPLAYED") "100")
      )
      (libsource (lib "SV601272A") (part "CMP-0021991-4"))
    )
    (comp (ref "R119")
      (value "Resistor")
      (footprint "0603R")
      (description "RES, 100, 1%, 0.1 W, AEC-Q200 Grade 0, 0603")
      (fields
        (field (name "PARTNUMBER") "CRCW0603100RFKEA")
        (field (name "MANUFACTURER") "Vishay-Dale")
        (field (name "VALUEDISPLAYED") "100")
      )
      (libsource (lib "SV601272A") (part "CMP-0021991-4"))
    )
    (comp (ref "R120")
      (value "Resistor")
      (footprint "0603R")
      (description "RES, 499, 1%, 0.1 W, AEC-Q200 Grade 0, 0603")
      (fields
        (field (name "PARTNUMBER") "CRCW0603499RFKEA")
        (field (name "MANUFACTURER") "Vishay-Dale")
        (field (name "VALUEDISPLAYED") "499")
      )
      (libsource (lib "SV601272A") (part "CMP-0022446-5"))
    )
    (comp (ref "R121")
      (value "Resistor")
      (footprint "0603R")
      (description "RES, 100 k, 1%, 0.1 W, AEC-Q200 Grade 0, 0603")
      (fields
        (field (name "PARTNUMBER") "CRCW0603100KFKEA")
        (field (name "MANUFACTURER") "Vishay-Dale")
        (field (name "VALUEDISPLAYED") "100k")
      )
      (libsource (lib "SV601272A") (part "CMP-0021990-4"))
    )
    (comp (ref "R122")
      (value "Resistor")
      (footprint "0603R")
      (description "RES, 100 k, 1%, 0.1 W, AEC-Q200 Grade 0, 0603")
      (fields
        (field (name "PARTNUMBER") "CRCW0603100KFKEA")
        (field (name "MANUFACTURER") "Vishay-Dale")
        (field (name "VALUEDISPLAYED") "100k")
      )
      (libsource (lib "SV601272A") (part "CMP-0021990-4"))
    )
    (comp (ref "R123")
      (value "Resistor")
      (footprint "0603R")
      (description "RES, 100 k, 1%, 0.1 W, AEC-Q200 Grade 0, 0603")
      (fields
        (field (name "PARTNUMBER") "CRCW0603100KFKEA")
        (field (name "MANUFACTURER") "Vishay-Dale")
        (field (name "VALUEDISPLAYED") "100k")
      )
      (libsource (lib "SV601272A") (part "CMP-0021990-4"))
    )
    (comp (ref "R124")
      (value "RC0603FR-071K5L")
      (footprint "0603R")
      (description "RES, 1.50 k, 1%, 0.1 W, 0603")
      (fields
        (field (name "MANUFACTURER") "Yageo America")
        (field (name "VALUEDISPLAYED") "1.50k")
        (field (name "PUBLISHER") "Texas Instruments")
      )
      (libsource (lib "SV601272A") (part "CMP-0022883-3"))
    )
    (comp (ref "R125")
      (value "Resistor")
      (footprint "0603R")
      (description "RES, 100, 1%, 0.1 W, AEC-Q200 Grade 0, 0603")
      (fields
        (field (name "PARTNUMBER") "CRCW0603100RFKEA")
        (field (name "MANUFACTURER") "Vishay-Dale")
        (field (name "VALUEDISPLAYED") "100")
      )
      (libsource (lib "SV601272A") (part "CMP-0021991-4"))
    )
    (comp (ref "R126")
      (value "RC0603FR-073K3L")
      (footprint "0603R")
      (description "RES, 3.30 k, 1%, 0.1 W, 0603")
      (fields
        (field (name "VALUEDISPLAYED") "3.30k")
        (field (name "MANUFACTURER") "Yageo America")
        (field (name "PUBLISHER") "Texas Instruments")
      )
      (libsource (lib "SV601272A") (part "Resistor"))
    )
    (comp (ref "R127")
      (value "Resistor")
      (footprint "0603R")
      (description "RES, 100, 1%, 0.1 W, AEC-Q200 Grade 0, 0603")
      (fields
        (field (name "PARTNUMBER") "CRCW0603100RFKEA")
        (field (name "MANUFACTURER") "Vishay-Dale")
        (field (name "VALUEDISPLAYED") "100")
      )
      (libsource (lib "SV601272A") (part "CMP-0021991-4"))
    )
    (comp (ref "R128")
      (value "Resistor")
      (footprint "0603R")
      (description "RES, 49.9, 1%, 0.1 W, AEC-Q200 Grade 0, 0603")
      (fields
        (field (name "PARTNUMBER") "CRCW060349R9FKEA")
        (field (name "MANUFACTURER") "Vishay-Dale")
        (field (name "VALUEDISPLAYED") "49.9")
      )
      (libsource (lib "SV601272A") (part "CMP-0022448-4"))
    )
    (comp (ref "R129")
      (value "RC0603FR-073K3L")
      (footprint "0603R")
      (description "RES, 3.30 k, 1%, 0.1 W, 0603")
      (fields
        (field (name "VALUEDISPLAYED") "3.30k")
        (field (name "MANUFACTURER") "Yageo America")
        (field (name "PUBLISHER") "Texas Instruments")
      )
      (libsource (lib "SV601272A") (part "Resistor"))
    )
    (comp (ref "R130")
      (value "Resistor")
      (footprint "0603R")
      (description "RES, 49.9, 1%, 0.1 W, AEC-Q200 Grade 0, 0603")
      (fields
        (field (name "PARTNUMBER") "CRCW060349R9FKEA")
        (field (name "MANUFACTURER") "Vishay-Dale")
        (field (name "VALUEDISPLAYED") "49.9")
      )
      (libsource (lib "SV601272A") (part "Resistor"))
    )
    (comp (ref "R131")
      (value "Resistor")
      (footprint "0603R")
      (description "RES, 100 k, 1%, 0.1 W, AEC-Q200 Grade 0, 0603")
      (fields
        (field (name "PARTNUMBER") "CRCW0603100KFKEA")
        (field (name "MANUFACTURER") "Vishay-Dale")
        (field (name "VALUEDISPLAYED") "100k")
      )
      (libsource (lib "SV601272A") (part "Resistor"))
    )
    (comp (ref "R132")
      (value "RC0603FR-071K5L")
      (footprint "0603R")
      (description "RES, 1.50 k, 1%, 0.1 W, 0603")
      (fields
        (field (name "MANUFACTURER") "Yageo America")
        (field (name "VALUEDISPLAYED") "1.50k")
        (field (name "PUBLISHER") "Texas Instruments")
      )
      (libsource (lib "SV601272A") (part "Resistor"))
    )
    (comp (ref "R133")
      (value "Resistor")
      (footprint "0603R")
      (description "RES, 0, 5%, 0.1 W, 0603")
      (fields
        (field (name "PARTNUMBER") "ERJ-3GEY0R00V")
        (field (name "MANUFACTURER") "Panasonic")
        (field (name "VALUEDISPLAYED") "0")
        (field (name "PUBLISHER") "Texas Instruments")
      )
      (libsource (lib "SV601272A") (part "Resistor"))
    )
    (comp (ref "R134")
      (value "Resistor")
      (footprint "0603R")
      (description "RES, 1.00, 1%, 0.1 W, AEC-Q200 Grade 0, 0603")
      (fields
        (field (name "PARTNUMBER") "CRCW06031R00FKEA")
        (field (name "VALUEDISPLAYED") "1.00")
        (field (name "MANUFACTURER") "Vishay-Dale")
      )
      (libsource (lib "SV601272A") (part "Resistor"))
    )
    (comp (ref "R135")
      (value "Resistor")
      (footprint "0603R")
      (description "RES, 0, 5%, 0.1 W, 0603")
      (fields
        (field (name "PARTNUMBER") "ERJ-3GEY0R00V")
        (field (name "MANUFACTURER") "Panasonic")
        (field (name "VALUEDISPLAYED") "0")
        (field (name "PUBLISHER") "Texas Instruments")
      )
      (libsource (lib "SV601272A") (part "CMP-0025874-3"))
    )
    (comp (ref "R136")
      (value "Resistor")
      (footprint "0603R")
      (description "RES, 0, 5%, 0.1 W, 0603")
      (fields
        (field (name "PARTNUMBER") "ERJ-3GEY0R00V")
        (field (name "MANUFACTURER") "Panasonic")
        (field (name "VALUEDISPLAYED") "0")
        (field (name "PUBLISHER") "Texas Instruments")
      )
      (libsource (lib "SV601272A") (part "CMP-0025874-3"))
    )
    (comp (ref "R137")
      (value "Resistor")
      (footprint "0603R")
      (description "RES, 1.00 M, 1%, 0.1 W, AEC-Q200 Grade 0, 0603")
      (fields
        (field (name "PARTNUMBER") "CRCW06031M00FKEA")
        (field (name "MANUFACTURER") "Vishay-Dale")
        (field (name "VALUEDISPLAYED") "1.00M")
      )
      (libsource (lib "SV601272A") (part "CMP-0022138-4"))
    )
    (comp (ref "R138")
      (value "Resistor")
      (footprint "0603R")
      (description "RES, 1.00 k, 1%, 0.1 W, AEC-Q200 Grade 0, 0603")
      (fields
        (field (name "PARTNUMBER") "CRCW06031K00FKEA")
        (field (name "MANUFACTURER") "Vishay-Dale")
        (field (name "VALUEDISPLAYED") "1.00k")
      )
      (libsource (lib "SV601272A") (part "CMP-0022109-5"))
    )
    (comp (ref "S1")
      (value "Switch_PushButton")
      (footprint "SW_TL1015AF160QG")
      (description "Switch, Tactile, SPST-NO, 0.05A, 12V, SMT")
      (fields
        (field (name "PARTNUMBER") "TL1015AF160QG")
        (field (name "MANUFACTURER") "E-Switch")
        (field (name "PUBLISHER") "Texas Instruments")
      )
      (libsource (lib "SV601272A") (part "Switch_PushButton"))
    )
    (comp (ref "U13")
      (value "TLV2711CDBVT")
      (footprint "DBV0005A_M")
      (fields (field (name "MANUFACTURER") "Texas Instruments"))
      (libsource (lib "Altium Content Vault") (part "TI-TLV27X1DBV5"))
    )
    (comp (ref "U17")
      (value "THS4524IDBT")
      (footprint "DBT0038A_M")
      (fields (field (name "MANUFACTURER") "Texas Instruments"))
      (libsource (lib "Altium Content Vault") (part "TI-THS4524-DBT38"))
    )
    (comp (ref "U21")
      (value "ADS131A04IPBSR")
      (footprint "PBS0032A_L")
      (description "24-Bit, 128kSPS, 4-Ch, Simultaneous Sampling, Delta-Sigma ADC, PBS0032A (TQFP-32)")
      (fields
        (field (name "ALTERNATE PARTNUMBER") "ADS131A04IPBS")
        (field (name "PARTNUMBER") "ADS131A04IPBSR")
        (field (name "MANUFACTURER") "Texas Instruments")
        (field (name "PUBLISHER") "Texas Instruments")
      )
      (libsource (lib "SV601272A") (part "ADS131A04"))
    )
    (comp (ref "U22")
      (value "TI-REF5025DGK8")
      (footprint "DGK0008A_N")
      (fields (field (name "PARTNUMBER") "REF5025IDGKR") (field (name "MANUFACTURER") "Texas Instruments"))
      (libsource (lib "SV601272A") (part "CMP-0032584-1"))
    )
    (comp (ref "VREF_ADC")
      (value "Pogo Pad")
      (footprint "PogoPad")
      (description "Pad for Pogo Pin Connector")
      (fields (field (name "SYMBOLCREATOR") "codlsc") (field (name "PUBLISHER") "Texas Instruments"))
      (libsource (lib "SV601272A") (part "PogoPad"))
    )
    (comp (ref "Y1")
      (value "XTAL_4P_13_G24")
      (footprint "CTS_407")
      (description "Crystal, 16.384 MHz, 20 pF, SMD")
      (fields
        (field (name "PARTNUMBER") "407F35E016M3840")
        (field (name "MANUFACTURER") "CTS Electrocomponents")
      )
      (libsource (lib "SV601272A") (part "XTAL_4P_13_G24"))
    )
  )
  (nets
    (net (code "3") (name "+3.3v") (class "Default")
      (node (ref "R121") (pin "2") (pinfunction "2_2") (pintype "passive"))
      (node (ref "R122") (pin "2") (pinfunction "2_2") (pintype "passive"))
      (node (ref "R123") (pin "2") (pinfunction "2_2") (pintype "passive"))
      (node (ref "U21") (pin "15") (pinfunction "IOVDD_15") (pintype "power_in"))
      (node (ref "U21") (pin "29") (pinfunction "IOVDD_29") (pintype "power_in"))
    )
    (net (code "4") (name "+5VA") (class "Default")
      (node (ref "C133") (pin "1") (pinfunction "1_1") (pintype "passive"))
      (node (ref "C134") (pin "1") (pinfunction "1_1") (pintype "passive"))
      (node (ref "C135") (pin "1") (pinfunction "1_1") (pintype "passive"))
      (node (ref "C136") (pin "1") (pinfunction "1_1") (pintype "passive"))
      (node (ref "C137") (pin "1") (pinfunction "1_1") (pintype "passive"))
      (node (ref "C138") (pin "1") (pinfunction "1_1") (pintype "passive"))
      (node (ref "C139") (pin "1") (pinfunction "1_1") (pintype "passive"))
      (node (ref "C140") (pin "1") (pinfunction "1_1") (pintype "passive"))
      (node (ref "C141") (pin "1") (pinfunction "1_1") (pintype "passive"))
      (node (ref "C19") (pin "1") (pinfunction "1_1") (pintype "passive"))
      (node (ref "C58") (pin "1") (pinfunction "1_1") (pintype "passive"))
      (node (ref "C59") (pin "1") (pinfunction "1_1") (pintype "passive"))
      (node (ref "C60") (pin "1") (pinfunction "1_1") (pintype "passive"))
      (node (ref "C61") (pin "1") (pinfunction "1_1") (pintype "passive"))
      (node (ref "C62") (pin "1") (pinfunction "1_1") (pintype "passive"))
      (node (ref "R116") (pin "2") (pinfunction "2_2") (pintype "passive"))
      (node (ref "R131") (pin "2") (pinfunction "2_2") (pintype "passive"))
      (node (ref "R50") (pin "2") (pinfunction "2_2") (pintype "passive"))
      (node (ref "R58") (pin "2") (pinfunction "2_2") (pintype "passive"))
      (node (ref "R70") (pin "1") (pinfunction "1_1") (pintype "passive"))
      (node (ref "U13") (pin "2") (pinfunction "VDD+_2") (pintype "power_in"))
      (node (ref "U17") (pin "20") (pinfunction "VS4+_20") (pintype "power_in"))
      (node (ref "U17") (pin "25") (pinfunction "VS3+_25") (pintype "power_in"))
      (node (ref "U17") (pin "30") (pinfunction "VS2+_30") (pintype "power_in"))
      (node (ref "U17") (pin "35") (pinfunction "VS1+_35") (pintype "power_in"))
      (node (ref "U21") (pin "9") (pinfunction "AVDD_9") (pintype "power_in"))
    )
    (net (code "5") (name "/ADC_SPI_CS") (class "Default")
      (node (ref "J19") (pin "5") (pinfunction "5_5") (pintype "passive"))
      (node (ref "U21") (pin "23") (pinfunction "CS_23") (pintype "input"))
    )
    (net (code "6") (name "/ADC_SPI_DONE") (class "Default")
      (node (ref "J19") (pin "11") (pinfunction "11_11") (pintype "passive"))
      (node (ref "R123") (pin "1") (pinfunction "1_1") (pintype "passive"))
      (node (ref "U21") (pin "18") (pinfunction "DONE_18") (pintype "output"))
    )
    (net (code "7") (name "/ADC_SPI_DRDY") (class "Default")
      (node (ref "J19") (pin "9") (pinfunction "9_9") (pintype "passive"))
      (node (ref "U21") (pin "19") (pinfunction "DRDY_19") (pintype "bidirectional"))
    )
    (net (code "8") (name "/ADC_SPI_MISO") (class "Default")
      (node (ref "J19") (pin "1") (pinfunction "1_1") (pintype "passive"))
      (node (ref "R122") (pin "1") (pinfunction "1_1") (pintype "passive"))
      (node (ref "U21") (pin "21") (pinfunction "DOUT_21") (pintype "output"))
    )
    (net (code "9") (name "/ADC_SPI_MOSI") (class "Default")
      (node (ref "J19") (pin "3") (pinfunction "3_3") (pintype "passive"))
      (node (ref "U21") (pin "20") (pinfunction "DIN_20") (pintype "input"))
    )
    (net (code "10") (name "/ADC_SPI_SCLK") (class "Default")
      (node (ref "J19") (pin "7") (pinfunction "7_7") (pintype "passive"))
      (node (ref "R138") (pin "2") (pinfunction "2_2") (pintype "passive"))
      (node (ref "U21") (pin "22") (pinfunction "SCLK_22") (pintype "bidirectional"))
    )
    (net (code "11") (name "/ADC_VCOM") (class "Default")
      (node (ref "C68") (pin "1") (pinfunction "1_1") (pintype "passive"))
      (node (ref "R20") (pin "1") (pinfunction "1_1") (pintype "passive"))
      (node (ref "R68") (pin "2") (pinfunction "2_2") (pintype "passive"))
      (node (ref "R72") (pin "1") (pinfunction "1_1") (pintype "passive"))
      (node (ref "R73") (pin "2") (pinfunction "2_2") (pintype "passive"))
      (node (ref "U13") (pin "1") (pinfunction "OUT_1") (pintype "output"))
      (node (ref "U13") (pin "4") (pinfunction "IN-_4") (pintype "input"))
    )
    (net (code "12") (name "/ADC_VREF") (class "Default")
      (node (ref "C155") (pin "1") (pinfunction "1_1") (pintype "passive"))
      (node (ref "R133") (pin "2") (pinfunction "2_2") (pintype "passive"))
      (node (ref "R3") (pin "1") (pinfunction "1_1") (pintype "passive"))
      (node (ref "U21") (pin "14") (pinfunction "REFEXT_14") (pintype "passive"))
    )
    (net (code "13") (name "/CS") (class "Default")
      (node (ref "J19") (pin "6") (pinfunction "6_6") (pintype "passive"))
    )
    (net (code "14") (name "/IBAT") (class "Default")
      (node (ref "R114") (pin "1") (pinfunction "1_1") (pintype "passive"))
      (node (ref "R48") (pin "1") (pinfunction "1_1") (pintype "passive"))
    )
    (net (code "15") (name "/IREF_VCOM") (class "Default")
      (node (ref "R112") (pin "1") (pinfunction "1_1") (pintype "passive"))
      (node (ref "R41") (pin "1") (pinfunction "1_1") (pintype "passive"))
    )
    (net (code "16") (name "/MISO") (class "Default")
      (node (ref "J19") (pin "2") (pinfunction "2_2") (pintype "passive"))
    )
    (net (code "17") (name "/MOSI") (class "Default")
      (node (ref "J19") (pin "4") (pinfunction "4_4") (pintype "passive"))
    )
    (net (code "18") (name "/SCLK") (class "Default")
      (node (ref "J19") (pin "8") (pinfunction "8_8") (pintype "passive"))
    )
    (net (code "19") (name "/SPI_DONE") (class "Default")
      (node (ref "J19") (pin "12") (pinfunction "12_12") (pintype "passive"))
    )
    (net (code "20") (name "/SPI_DRDY") (class "Default")
      (node (ref "J19") (pin "10") (pinfunction "10_10") (pintype "passive"))
    )
    (net (code "21") (name "/VBAT") (class "Default")
      (node (ref "R129") (pin "1") (pinfunction "1_1") (pintype "passive"))
      (node (ref "R56") (pin "1") (pinfunction "1_1") (pintype "passive"))
    )
    (net (code "24") (name "AGND") (class "Default")
      (node (ref "C13") (pin "2") (pinfunction "2_2") (pintype "passive"))
      (node (ref "C131") (pin "2") (pinfunction "2_2") (pintype "passive"))
      (node (ref "C132") (pin "2") (pinfunction "2_2") (pintype "passive"))
      (node (ref "C133") (pin "2") (pinfunction "2_2") (pintype "passive"))
      (node (ref "C134") (pin "2") (pinfunction "2_2") (pintype "passive"))
      (node (ref "C135") (pin "2") (pinfunction "2_2") (pintype "passive"))
      (node (ref "C136") (pin "2") (pinfunction "2_2") (pintype "passive"))
      (node (ref "C137") (pin "2") (pinfunction "2_2") (pintype "passive"))
      (node (ref "C138") (pin "2") (pinfunction "2_2") (pintype "passive"))
      (node (ref "C139") (pin "2") (pinfunction "2_2") (pintype "passive"))
      (node (ref "C14") (pin "2") (pinfunction "2_2") (pintype "passive"))
      (node (ref "C140") (pin "2") (pinfunction "2_2") (pintype "passive"))
      (node (ref "C141") (pin "2") (pinfunction "2_2") (pintype "passive"))
      (node (ref "C145") (pin "1") (pinfunction "1_1") (pintype "passive"))
      (node (ref "C146") (pin "1") (pinfunction "1_1") (pintype "passive"))
      (node (ref "C149") (pin "1") (pinfunction "1_1") (pintype "passive"))
      (node (ref "C152") (pin "2") (pinfunction "2_2") (pintype "passive"))
      (node (ref "C153") (pin "2") (pinfunction "2_2") (pintype "passive"))
      (node (ref "C155") (pin "2") (pinfunction "2_2") (pintype "passive"))
      (node (ref "C156") (pin "2") (pinfunction "2_2") (pintype "passive"))
      (node (ref "C157") (pin "2") (pinfunction "2_2") (pintype "passive"))
      (node (ref "C158") (pin "2") (pinfunction "2_2") (pintype "passive"))
      (node (ref "C159") (pin "2") (pinfunction "2_2") (pintype "passive"))
      (node (ref "C160") (pin "2") (pinfunction "2_2") (pintype "passive"))
      (node (ref "C161") (pin "2") (pinfunction "2_2") (pintype "passive"))
      (node (ref "C19") (pin "2") (pinfunction "2_2") (pintype "passive"))
      (node (ref "C58") (pin "2") (pinfunction "2_2") (pintype "passive"))
      (node (ref "C59") (pin "2") (pinfunction "2_2") (pintype "passive"))
      (node (ref "C60") (pin "2") (pinfunction "2_2") (pintype "passive"))
      (node (ref "C61") (pin "2") (pinfunction "2_2") (pintype "passive"))
      (node (ref "C62") (pin "2") (pinfunction "2_2") (pintype "passive"))
      (node (ref "C67") (pin "2") (pinfunction "2_2") (pintype "passive"))
      (node (ref "C68") (pin "2") (pinfunction "2_2") (pintype "passive"))
      (node (ref "J19") (pin "13") (pinfunction "13_13") (pintype "passive"))
      (node (ref "J19") (pin "14") (pinfunction "14_14") (pintype "passive"))
      (node (ref "J19") (pin "15") (pinfunction "15_15") (pintype "passive"))
      (node (ref "R126") (pin "1") (pinfunction "1_1") (pintype "passive"))
      (node (ref "R138") (pin "1") (pinfunction "1_1") (pintype "passive"))
      (node (ref "R55") (pin "1") (pinfunction "1_1") (pintype "passive"))
      (node (ref "R71") (pin "2") (pinfunction "2_2") (pintype "passive"))
      (node (ref "S1") (pin "2") (pinfunction "2_2") (pintype "passive"))
      (node (ref "U13") (pin "5") (pinfunction "VDD-/GND_5") (pintype "power_in"))
      (node (ref "U17") (pin "10") (pinfunction "VS-_10") (pintype "power_in"))
      (node (ref "U17") (pin "15") (pinfunction "VS-_15") (pintype "power_in"))
      (node (ref "U17") (pin "23") (pinfunction "VS-_23") (pintype "power_in"))
      (node (ref "U17") (pin "24") (pinfunction "VS-_24") (pintype "power_in"))
      (node (ref "U17") (pin "28") (pinfunction "VS-_28") (pintype "power_in"))
      (node (ref "U17") (pin "29") (pinfunction "VS-_29") (pintype "power_in"))
      (node (ref "U17") (pin "33") (pinfunction "VS-_33") (pintype "power_in"))
      (node (ref "U17") (pin "34") (pinfunction "VS-_34") (pintype "power_in"))
      (node (ref "U17") (pin "38") (pinfunction "VS-_38") (pintype "power_in"))
      (node (ref "U17") (pin "5") (pinfunction "VS-_5") (pintype "power_in"))
      (node (ref "U21") (pin "10") (pinfunction "AVSS_10") (pintype "power_in"))
      (node (ref "U21") (pin "11") (pinfunction "VNCP_11") (pintype "power_in"))
      (node (ref "U21") (pin "13") (pinfunction "VREFN_13") (pintype "input"))
      (node (ref "U21") (pin "27") (pinfunction "GND_27") (pintype "power_in"))
      (node (ref "U21") (pin "31") (pinfunction "M1_31") (pintype "passive"))
      (node (ref "U21") (pin "32") (pinfunction "M2_32") (pintype "passive"))
      (node (ref "U22") (pin "4") (pinfunction "GND_4") (pintype "power_in"))
      (node (ref "Y1") (pin "2") (pinfunction "GND_2") (pintype "power_in"))
      (node (ref "Y1") (pin "4") (pinfunction "GND_4") (pintype "power_in"))
    )
    (net (code "25") (name "Net-(C63-Pad1)") (class "Default")
      (node (ref "C63") (pin "1") (pinfunction "1_1") (pintype "passive"))
      (node (ref "R13") (pin "2") (pinfunction "2_2") (pintype "passive"))
    )
    (net (code "26") (name "Net-(C63-Pad2)") (class "Default")
      (node (ref "C63") (pin "2") (pinfunction "2_2") (pintype "passive"))
      (node (ref "R1") (pin "1") (pinfunction "1_1") (pintype "passive"))
      (node (ref "R20") (pin "2") (pinfunction "2_2") (pintype "passive"))
    )
    (net (code "27") (name "Net-(C65-Pad1)") (class "Default")
      (node (ref "C65") (pin "1") (pinfunction "1_1") (pintype "passive"))
      (node (ref "R69") (pin "2") (pinfunction "2_2") (pintype "passive"))
    )
    (net (code "28") (name "Net-(C65-Pad2)") (class "Default")
      (node (ref "C65") (pin "2") (pinfunction "2_2") (pintype "passive"))
      (node (ref "R2") (pin "1") (pinfunction "1_1") (pintype "passive"))
      (node (ref "R68") (pin "1") (pinfunction "1_1") (pintype "passive"))
    )
    (net (code "29") (name "Net-(C66-Pad1)") (class "Default")
      (node (ref "C66") (pin "1") (pinfunction "1_1") (pintype "passive"))
      (node (ref "R46") (pin "2") (pinfunction "2_2") (pintype "passive"))
    )
    (net (code "30") (name "Net-(C66-Pad2)") (class "Default")
      (node (ref "C66") (pin "2") (pinfunction "2_2") (pintype "passive"))
      (node (ref "R5") (pin "1") (pinfunction "1_1") (pintype "passive"))
      (node (ref "R72") (pin "2") (pinfunction "2_2") (pintype "passive"))
    )
    (net (code "31") (name "Net-(C69-Pad1)") (class "Default")
      (node (ref "C69") (pin "1") (pinfunction "1_1") (pintype "passive"))
      (node (ref "R51") (pin "2") (pinfunction "2_2") (pintype "passive"))
    )
    (net (code "32") (name "Net-(C69-Pad2)") (class "Default")
      (node (ref "C69") (pin "2") (pinfunction "2_2") (pintype "passive"))
      (node (ref "R6") (pin "1") (pinfunction "1_1") (pintype "passive"))
      (node (ref "R73") (pin "1") (pinfunction "1_1") (pintype "passive"))
    )
    (net (code "33") (name "Net-(C152-Pad1)") (class "Default")
      (node (ref "C152") (pin "1") (pinfunction "1_1") (pintype "passive"))
      (node (ref "R135") (pin "2") (pinfunction "2_2") (pintype "passive"))
      (node (ref "Y1") (pin "1") (pinfunction "1_1") (pintype "passive"))
    )
    (net (code "34") (name "Net-(C153-Pad1)") (class "Default")
      (node (ref "C153") (pin "1") (pinfunction "1_1") (pintype "passive"))
      (node (ref "R136") (pin "1") (pinfunction "1_1") (pintype "passive"))
      (node (ref "Y1") (pin "3") (pinfunction "3_3") (pintype "passive"))
    )
    (net (code "35") (name "Net-(C161-Pad1)") (class "Default")
      (node (ref "C161") (pin "1") (pinfunction "1_1") (pintype "passive"))
      (node (ref "R134") (pin "1") (pinfunction "1_1") (pintype "passive"))
    )
    (net (code "36") (name "Net-(R12-Pad2)") (class "Default")
      (node (ref "R12") (pin "2") (pinfunction "2_2") (pintype "passive"))
      (node (ref "R13") (pin "1") (pinfunction "1_1") (pintype "passive"))
      (node (ref "R40") (pin "2") (pinfunction "2_2") (pintype "passive"))
    )
    (net (code "37") (name "Net-(R46-Pad1)") (class "Default")
      (node (ref "R46") (pin "1") (pinfunction "1_1") (pintype "passive"))
      (node (ref "R53") (pin "2") (pinfunction "2_2") (pintype "passive"))
      (node (ref "R54") (pin "2") (pinfunction "2_2") (pintype "passive"))
    )
    (net (code "38") (name "Net-(R49-Pad2)") (class "Default")
      (node (ref "R49") (pin "2") (pinfunction "2_2") (pintype "passive"))
      (node (ref "R52") (pin "2") (pinfunction "2_2") (pintype "passive"))
      (node (ref "R69") (pin "1") (pinfunction "1_1") (pintype "passive"))
    )
    (net (code "39") (name "Net-(R51-Pad1)") (class "Default")
      (node (ref "R51") (pin "1") (pinfunction "1_1") (pintype "passive"))
      (node (ref "R57") (pin "2") (pinfunction "2_2") (pintype "passive"))
      (node (ref "R59") (pin "2") (pinfunction "2_2") (pintype "passive"))
    )
    (net (code "40") (name "Net-(R111-Pad2)") (class "Default")
      (node (ref "R111") (pin "2") (pinfunction "2_2") (pintype "passive"))
      (node (ref "R113") (pin "2") (pinfunction "2_2") (pintype "passive"))
      (node (ref "R119") (pin "1") (pinfunction "1_1") (pintype "passive"))
    )
    (net (code "41") (name "Net-(R115-Pad2)") (class "Default")
      (node (ref "R115") (pin "2") (pinfunction "2_2") (pintype "passive"))
      (node (ref "R117") (pin "2") (pinfunction "2_2") (pintype "passive"))
      (node (ref "R118") (pin "1") (pinfunction "1_1") (pintype "passive"))
    )
    (net (code "42") (name "Net-(R124-Pad2)") (class "Default")
      (node (ref "R124") (pin "2") (pinfunction "2_2") (pintype "passive"))
      (node (ref "R127") (pin "1") (pinfunction "1_1") (pintype "passive"))
      (node (ref "R128") (pin "2") (pinfunction "2_2") (pintype "passive"))
    )
    (net (code "43") (name "Net-(R125-Pad1)") (class "Default")
      (node (ref "R125") (pin "1") (pinfunction "1_1") (pintype "passive"))
      (node (ref "R130") (pin "2") (pinfunction "2_2") (pintype "passive"))
      (node (ref "R132") (pin "2") (pinfunction "2_2") (pintype "passive"))
    )
    (net (code "44") (name "Net-(U13-IN+)") (class "Default")
      (node (ref "C67") (pin "1") (pinfunction "1_1") (pintype "passive"))
      (node (ref "R3") (pin "2") (pinfunction "2_2") (pintype "passive"))
      (node (ref "R70") (pin "2") (pinfunction "2_2") (pintype "passive"))
      (node (ref "R71") (pin "1") (pinfunction "1_1") (pintype "passive"))
      (node (ref "U13") (pin "3") (pinfunction "IN+_3") (pintype "input"))
    )
    (net (code "45") (name "Net-(U17A-VIN1+)") (class "Default")
      (node (ref "C143") (pin "2") (pinfunction "2_2") (pintype "passive"))
      (node (ref "C144") (pin "1") (pinfunction "1_1") (pintype "passive"))
      (node (ref "R114") (pin "2") (pinfunction "2_2") (pintype "passive"))
      (node (ref "R117") (pin "1") (pinfunction "1_1") (pintype "passive"))
      (node (ref "U17") (pin "2") (pinfunction "VIN1+_2") (pintype "input"))
    )
    (net (code "46") (name "Net-(U17A-VIN1-)") (class "Default")
      (node (ref "C142") (pin "1") (pinfunction "1_1") (pintype "passive"))
      (node (ref "C143") (pin "1") (pinfunction "1_1") (pintype "passive"))
      (node (ref "R111") (pin "1") (pinfunction "1_1") (pintype "passive"))
      (node (ref "R112") (pin "2") (pinfunction "2_2") (pintype "passive"))
      (node (ref "U17") (pin "3") (pinfunction "VIN1-_3") (pintype "input"))
    )
    (net (code "47") (name "Net-(U17A-VOCM1)") (class "Default")
      (node (ref "R116") (pin "1") (pinfunction "1_1") (pintype "passive"))
      (node (ref "U17") (pin "4") (pinfunction "VOCM1_4") (pintype "input"))
    )
    (net (code "48") (name "Net-(U17A-VOUT1+)") (class "Default")
      (node (ref "C142") (pin "2") (pinfunction "2_2") (pintype "passive"))
      (node (ref "R113") (pin "1") (pinfunction "1_1") (pintype "passive"))
      (node (ref "U17") (pin "36") (pinfunction "VOUT1+_36") (pintype "output"))
    )
    (net (code "49") (name "Net-(U17A-VOUT1-)") (class "Default")
      (node (ref "C144") (pin "2") (pinfunction "2_2") (pintype "passive"))
      (node (ref "R115") (pin "1") (pinfunction "1_1") (pintype "passive"))
      (node (ref "U17") (pin "37") (pinfunction "VOUT1-_37") (pintype "output"))
    )
    (net (code "50") (name "Net-(U17B-VIN2+)") (class "Default")
      (node (ref "C151") (pin "2") (pinfunction "2_2") (pintype "passive"))
      (node (ref "C154") (pin "1") (pinfunction "1_1") (pintype "passive"))
      (node (ref "R129") (pin "2") (pinfunction "2_2") (pintype "passive"))
      (node (ref "R132") (pin "1") (pinfunction "1_1") (pintype "passive"))
      (node (ref "U17") (pin "7") (pinfunction "VIN2+_7") (pintype "input"))
    )
    (net (code "51") (name "Net-(U17B-VIN2-)") (class "Default")
      (node (ref "C150") (pin "1") (pinfunction "1_1") (pintype "passive"))
      (node (ref "C151") (pin "1") (pinfunction "1_1") (pintype "passive"))
      (node (ref "R124") (pin "1") (pinfunction "1_1") (pintype "passive"))
      (node (ref "R126") (pin "2") (pinfunction "2_2") (pintype "passive"))
      (node (ref "U17") (pin "8") (pinfunction "VIN2-_8") (pintype "input"))
    )
    (net (code "52") (name "Net-(U17B-VOCM2)") (class "Default")
      (node (ref "R131") (pin "1") (pinfunction "1_1") (pintype "passive"))
      (node (ref "U17") (pin "9") (pinfunction "VOCM2_9") (pintype "input"))
    )
    (net (code "53") (name "Net-(U17B-VOUT2+)") (class "Default")
      (node (ref "C150") (pin "2") (pinfunction "2_2") (pintype "passive"))
      (node (ref "R128") (pin "1") (pinfunction "1_1") (pintype "passive"))
      (node (ref "U17") (pin "31") (pinfunction "VOUT2+_31") (pintype "output"))
    )
    (net (code "54") (name "Net-(U17B-VOUT2-)") (class "Default")
      (node (ref "C154") (pin "2") (pinfunction "2_2") (pintype "passive"))
      (node (ref "R130") (pin "1") (pinfunction "1_1") (pintype "passive"))
      (node (ref "U17") (pin "32") (pinfunction "VOUT2-_32") (pintype "output"))
    )
    (net (code "55") (name "Net-(U17C-VIN3+)") (class "Default")
      (node (ref "C21") (pin "2") (pinfunction "2_2") (pintype "passive"))
      (node (ref "C25") (pin "1") (pinfunction "1_1") (pintype "passive"))
      (node (ref "R48") (pin "2") (pinfunction "2_2") (pintype "passive"))
      (node (ref "R52") (pin "1") (pinfunction "1_1") (pintype "passive"))
      (node (ref "U17") (pin "12") (pinfunction "VIN3+_12") (pintype "input"))
    )
    (net (code "56") (name "Net-(U17C-VIN3-)") (class "Default")
      (node (ref "C18") (pin "1") (pinfunction "1_1") (pintype "passive"))
      (node (ref "C21") (pin "1") (pinfunction "1_1") (pintype "passive"))
      (node (ref "R12") (pin "1") (pinfunction "1_1") (pintype "passive"))
      (node (ref "R41") (pin "2") (pinfunction "2_2") (pintype "passive"))
      (node (ref "U17") (pin "13") (pinfunction "VIN3-_13") (pintype "input"))
    )
    (net (code "57") (name "Net-(U17C-VOCM3)") (class "Default")
      (node (ref "R50") (pin "1") (pinfunction "1_1") (pintype "passive"))
      (node (ref "U17") (pin "14") (pinfunction "VOCM3_14") (pintype "input"))
    )
    (net (code "58") (name "Net-(U17C-VOUT3+)") (class "Default")
      (node (ref "C18") (pin "2") (pinfunction "2_2") (pintype "passive"))
      (node (ref "R40") (pin "1") (pinfunction "1_1") (pintype "passive"))
      (node (ref "U17") (pin "26") (pinfunction "VOUT3+_26") (pintype "output"))
    )
    (net (code "59") (name "Net-(U17C-VOUT3-)") (class "Default")
      (node (ref "C25") (pin "2") (pinfunction "2_2") (pintype "passive"))
      (node (ref "R49") (pin "1") (pinfunction "1_1") (pintype "passive"))
      (node (ref "U17") (pin "27") (pinfunction "VOUT3-_27") (pintype "output"))
    )
    (net (code "60") (name "Net-(U17D-VIN4+)") (class "Default")
      (node (ref "C41") (pin "2") (pinfunction "2_2") (pintype "passive"))
      (node (ref "C42") (pin "1") (pinfunction "1_1") (pintype "passive"))
      (node (ref "R56") (pin "2") (pinfunction "2_2") (pintype "passive"))
      (node (ref "R59") (pin "1") (pinfunction "1_1") (pintype "passive"))
      (node (ref "U17") (pin "17") (pinfunction "VIN4+_17") (pintype "input"))
    )
    (net (code "61") (name "Net-(U17D-VIN4-)") (class "Default")
      (node (ref "C27") (pin "1") (pinfunction "1_1") (pintype "passive"))
      (node (ref "C41") (pin "1") (pinfunction "1_1") (pintype "passive"))
      (node (ref "R53") (pin "1") (pinfunction "1_1") (pintype "passive"))
      (node (ref "R55") (pin "2") (pinfunction "2_2") (pintype "passive"))
      (node (ref "U17") (pin "18") (pinfunction "VIN4-_18") (pintype "input"))
    )
    (net (code "62") (name "Net-(U17D-VOCM4)") (class "Default")
      (node (ref "R58") (pin "1") (pinfunction "1_1") (pintype "passive"))
      (node (ref "U17") (pin "19") (pinfunction "VOCM4_19") (pintype "input"))
    )
    (net (code "63") (name "Net-(U17D-VOUT4+)") (class "Default")
      (node (ref "C27") (pin "2") (pinfunction "2_2") (pintype "passive"))
      (node (ref "R54") (pin "1") (pinfunction "1_1") (pintype "passive"))
      (node (ref "U17") (pin "21") (pinfunction "VOUT4+_21") (pintype "output"))
    )
    (net (code "64") (name "Net-(U17D-VOUT4-)") (class "Default")
      (node (ref "C42") (pin "2") (pinfunction "2_2") (pintype "passive"))
      (node (ref "R57") (pin "1") (pinfunction "1_1") (pintype "passive"))
      (node (ref "U17") (pin "22") (pinfunction "VOUT4-_22") (pintype "output"))
    )
    (net (code "65") (name "Net-(U21-AIN1N)") (class "Default")
      (node (ref "C147") (pin "1") (pinfunction "1_1") (pintype "passive"))
      (node (ref "R118") (pin "2") (pinfunction "2_2") (pintype "passive"))
      (node (ref "U21") (pin "1") (pinfunction "AIN1N_1") (pintype "input"))
    )
    (net (code "66") (name "Net-(U21-AIN1P)") (class "Default")
      (node (ref "C147") (pin "2") (pinfunction "2_2") (pintype "passive"))
      (node (ref "R119") (pin "2") (pinfunction "2_2") (pintype "passive"))
      (node (ref "U21") (pin "2") (pinfunction "AIN1P_2") (pintype "input"))
    )
    (net (code "67") (name "Net-(U21-AIN2N)") (class "Default")
      (node (ref "C148") (pin "1") (pinfunction "1_1") (pintype "passive"))
      (node (ref "R125") (pin "2") (pinfunction "2_2") (pintype "passive"))
      (node (ref "U21") (pin "3") (pinfunction "AIN2N_3") (pintype "input"))
    )
    (net (code "68") (name "Net-(U21-AIN2P)") (class "Default")
      (node (ref "C148") (pin "2") (pinfunction "2_2") (pintype "passive"))
      (node (ref "R127") (pin "2") (pinfunction "2_2") (pintype "passive"))
      (node (ref "U21") (pin "4") (pinfunction "AIN2P_4") (pintype "input"))
    )
    (net (code "69") (name "Net-(U21-AIN3N)") (class "Default")
      (node (ref "C64") (pin "2") (pinfunction "2_2") (pintype "passive"))
      (node (ref "R2") (pin "2") (pinfunction "2_2") (pintype "passive"))
      (node (ref "U21") (pin "5") (pinfunction "AIN3N_5") (pintype "input"))
    )
    (net (code "70") (name "Net-(U21-AIN3P)") (class "Default")
      (node (ref "C64") (pin "1") (pinfunction "1_1") (pintype "passive"))
      (node (ref "R1") (pin "2") (pinfunction "2_2") (pintype "passive"))
      (node (ref "U21") (pin "6") (pinfunction "AIN3P_6") (pintype "input"))
    )
    (net (code "71") (name "Net-(U21-AIN4N)") (class "Default")
      (node (ref "C23") (pin "2") (pinfunction "2_2") (pintype "passive"))
      (node (ref "R6") (pin "2") (pinfunction "2_2") (pintype "passive"))
      (node (ref "U21") (pin "7") (pinfunction "AIN4N_7") (pintype "input"))
    )
    (net (code "72") (name "Net-(U21-AIN4P)") (class "Default")
      (node (ref "C23") (pin "1") (pinfunction "1_1") (pintype "passive"))
      (node (ref "R5") (pin "2") (pinfunction "2_2") (pintype "passive"))
      (node (ref "U21") (pin "8") (pinfunction "AIN4P_8") (pintype "input"))
    )
    (net (code "73") (name "Net-(U21-CAP)") (class "Default")
      (node (ref "C156") (pin "1") (pinfunction "1_1") (pintype "passive"))
      (node (ref "U21") (pin "28") (pinfunction "CAP_28") (pintype "passive"))
    )
    (net (code "74") (name "Net-(U21-CLKIN{slash}XTAL1)") (class "Default")
      (node (ref "R135") (pin "1") (pinfunction "1_1") (pintype "passive"))
      (node (ref "R137") (pin "2") (pinfunction "2_2") (pintype "passive"))
      (node (ref "U21") (pin "25") (pinfunction "CLKIN/XTAL1_25") (pintype "input"))
    )
    (net (code "75") (name "Net-(U21-M0)") (class "Default")
      (node (ref "R120") (pin "1") (pinfunction "1_1") (pintype "passive"))
      (node (ref "U21") (pin "30") (pinfunction "M0_30") (pintype "passive"))
    )
    (net (code "76") (name "Net-(U21-RESET)") (class "Default")
      (node (ref "C149") (pin "2") (pinfunction "2_2") (pintype "passive"))
      (node (ref "R121") (pin "1") (pinfunction "1_1") (pintype "passive"))
      (node (ref "S1") (pin "1") (pinfunction "1_1") (pintype "passive"))
      (node (ref "U21") (pin "17") (pinfunction "RESET_17") (pintype "input"))
    )
    (net (code "77") (name "Net-(U21-VREFP)") (class "Default")
      (node (ref "C145") (pin "2") (pinfunction "2_2") (pintype "passive"))
      (node (ref "C146") (pin "2") (pinfunction "2_2") (pintype "passive"))
      (node (ref "U21") (pin "12") (pinfunction "VREFP_12") (pintype "input"))
    )
    (net (code "78") (name "Net-(U21-XTAL2)") (class "Default")
      (node (ref "R136") (pin "2") (pinfunction "2_2") (pintype "passive"))
      (node (ref "R137") (pin "1") (pinfunction "1_1") (pintype "passive"))
      (node (ref "U21") (pin "26") (pinfunction "XTAL2_26") (pintype "output"))
    )
    (net (code "79") (name "Net-(U22A-TRIM{slash}NR)") (class "Default")
      (node (ref "C157") (pin "1") (pinfunction "1_1") (pintype "passive"))
      (node (ref "U22") (pin "5") (pinfunction "TRIM/NR_5") (pintype "input"))
    )
    (net (code "80") (name "Net-(U22A-VOUT)") (class "Default")
      (node (ref "C158") (pin "1") (pinfunction "1_1") (pintype "passive"))
      (node (ref "C159") (pin "1") (pinfunction "1_1") (pintype "passive"))
      (node (ref "R133") (pin "1") (pinfunction "1_1") (pintype "passive"))
      (node (ref "R134") (pin "2") (pinfunction "2_2") (pintype "passive"))
      (node (ref "U22") (pin "6") (pinfunction "VOUT_6") (pintype "output"))
      (node (ref "VREF_ADC") (pin "1") (pintype "passive"))
    )
    (net (code "81") (name "V3.3_DIGITAL") (class "Default")
      (node (ref "R120") (pin "2") (pinfunction "2_2") (pintype "passive"))
      (node (ref "U21") (pin "16") (pinfunction "RESV_16") (pintype "passive"))
    )
    (net (code "82") (name "V5.0_DAQ") (class "Default")
      (node (ref "C160") (pin "1") (pinfunction "1_1") (pintype "passive"))
      (node (ref "U22") (pin "2") (pinfunction "VIN_2") (pintype "power_in"))
    )
    (net (code "83") (name "Vocm1") (class "Default")
      (node (ref "C131") (pin "1") (pinfunction "1_1") (pintype "passive"))
      (node (ref "U17") (pin "1") (pinfunction "~{PD}1_1") (pintype "input"))
    )
    (net (code "84") (name "Vocm2") (class "Default")
      (node (ref "C132") (pin "1") (pinfunction "1_1") (pintype "passive"))
      (node (ref "U17") (pin "6") (pinfunction "~{PD}2_6") (pintype "input"))
    )
    (net (code "85") (name "Vocm3") (class "Default")
      (node (ref "C13") (pin "1") (pinfunction "1_1") (pintype "passive"))
      (node (ref "U17") (pin "11") (pinfunction "~{PD}3_11") (pintype "input"))
    )
    (net (code "86") (name "Vocm4") (class "Default")
      (node (ref "C14") (pin "1") (pinfunction "1_1") (pintype "passive"))
      (node (ref "U17") (pin "16") (pinfunction "~{PD}4_16") (pintype "input"))
    )
    (net (code "87") (name "unconnected-(J19-Pad16)") (class "Default")
      (node (ref "J19") (pin "16") (pinfunction "16_16") (pintype "passive"))
    )
    (net (code "88") (name "unconnected-(U21-NC-Pad24)") (class "Default")
      (node (ref "U21") (pin "24") (pinfunction "NC_24") (pintype "passive"))
    )
    (net (code "89") (name "unconnected-(U22A-TEMP-Pad3)") (class "Default")
      (node (ref "U22") (pin "3") (pinfunction "TEMP_3") (pintype "output"))
    )
  )
)
